# PART1.net
KiCad netlist of a schematic drawn in Altium Designer
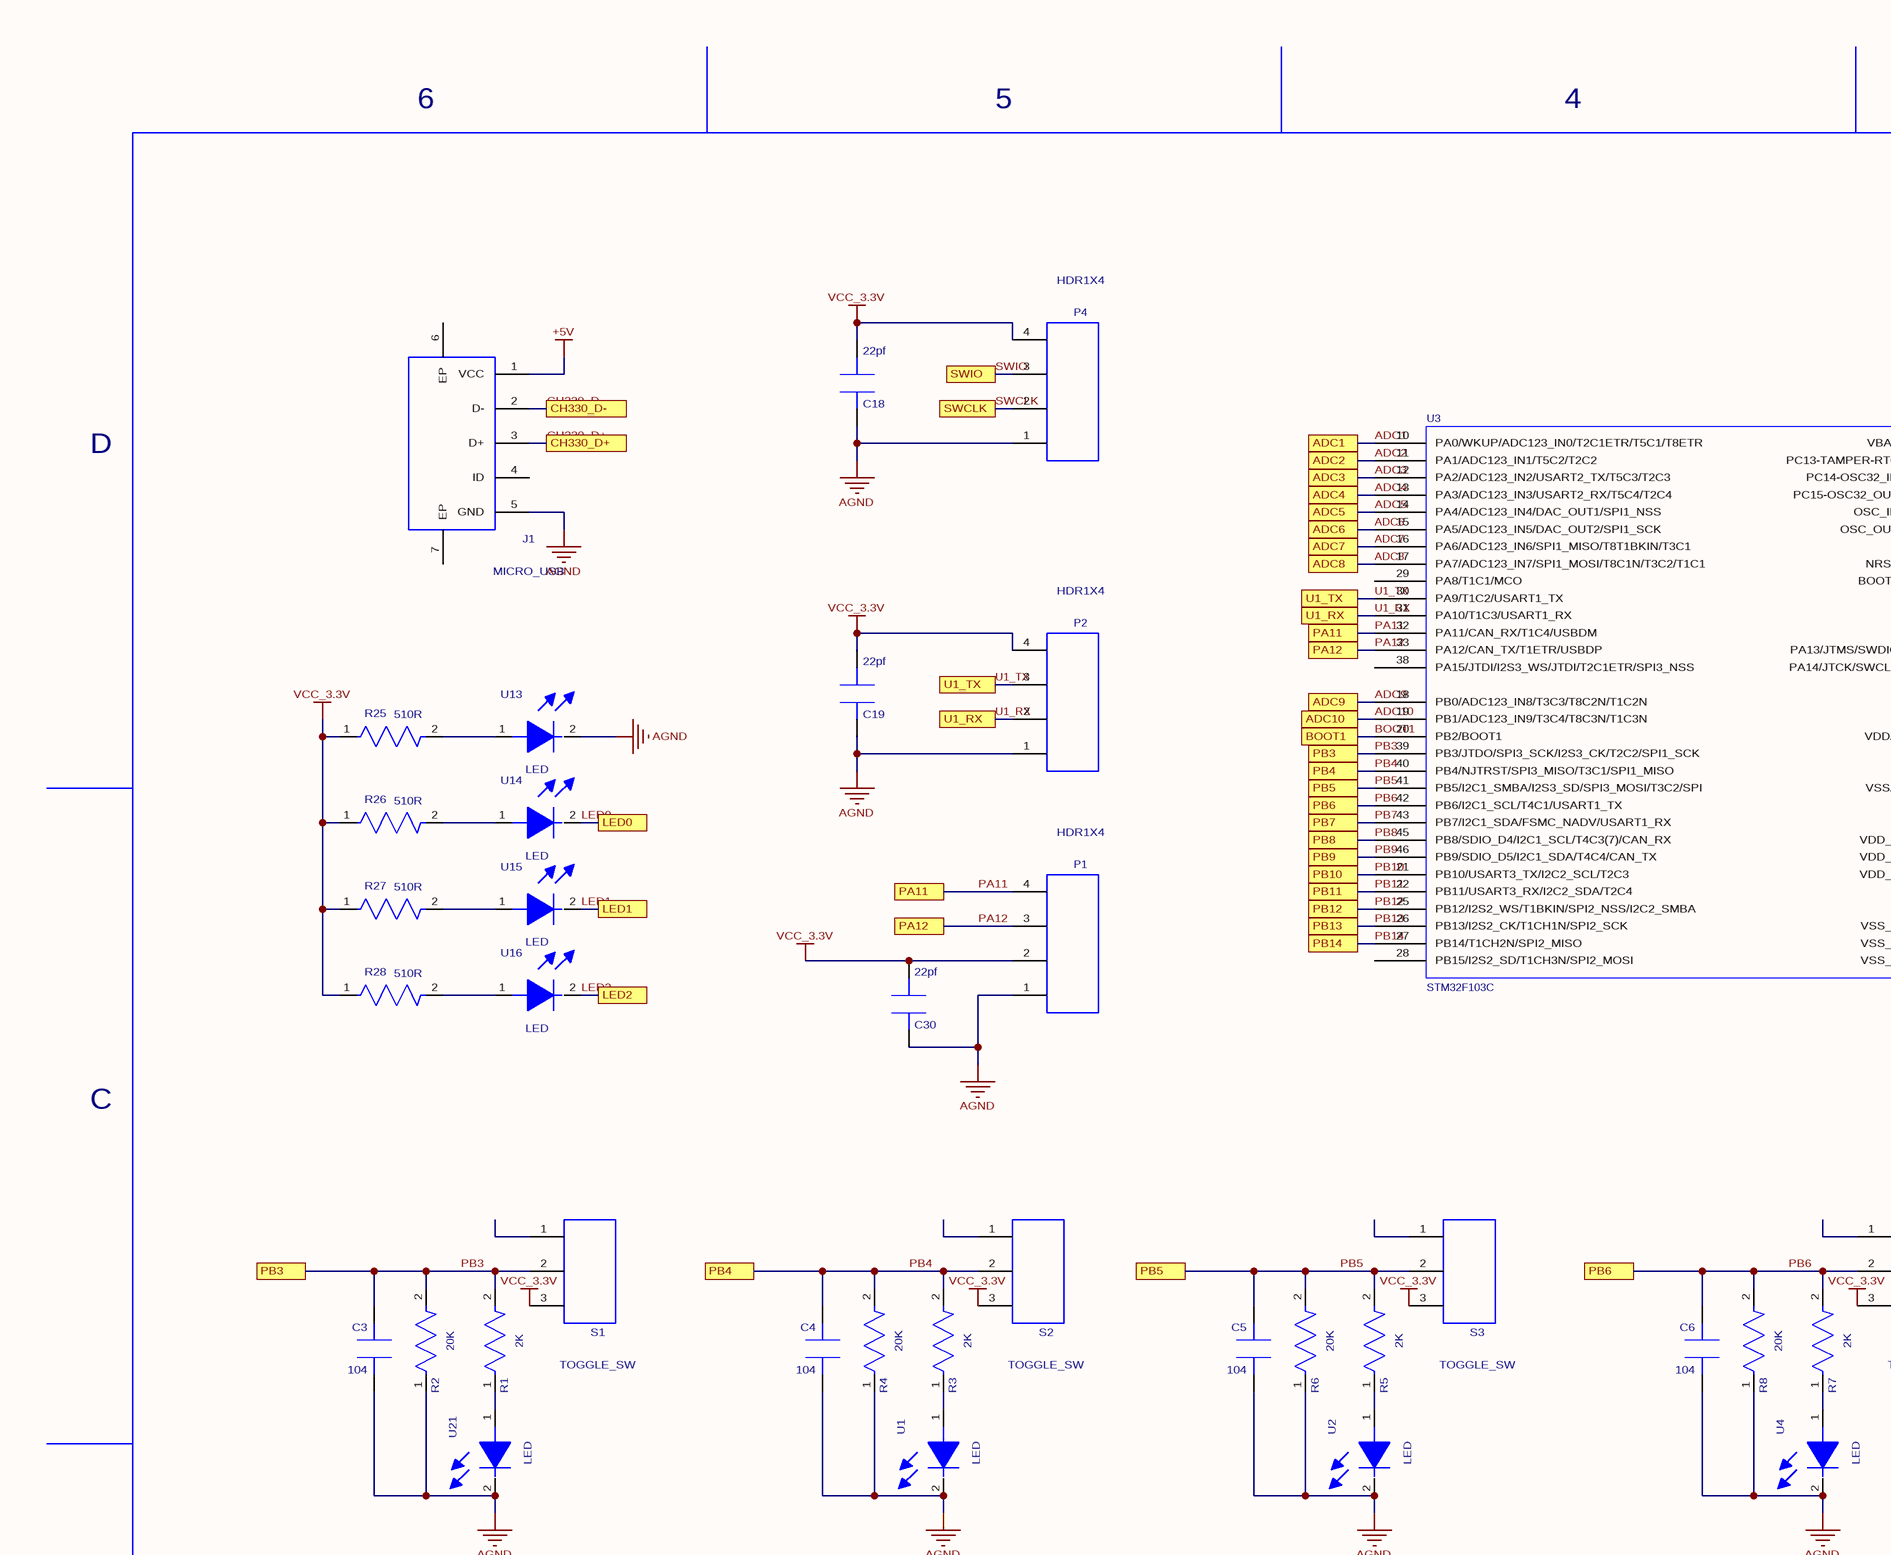
[diagram p0: PART1.SchDoc, top left]
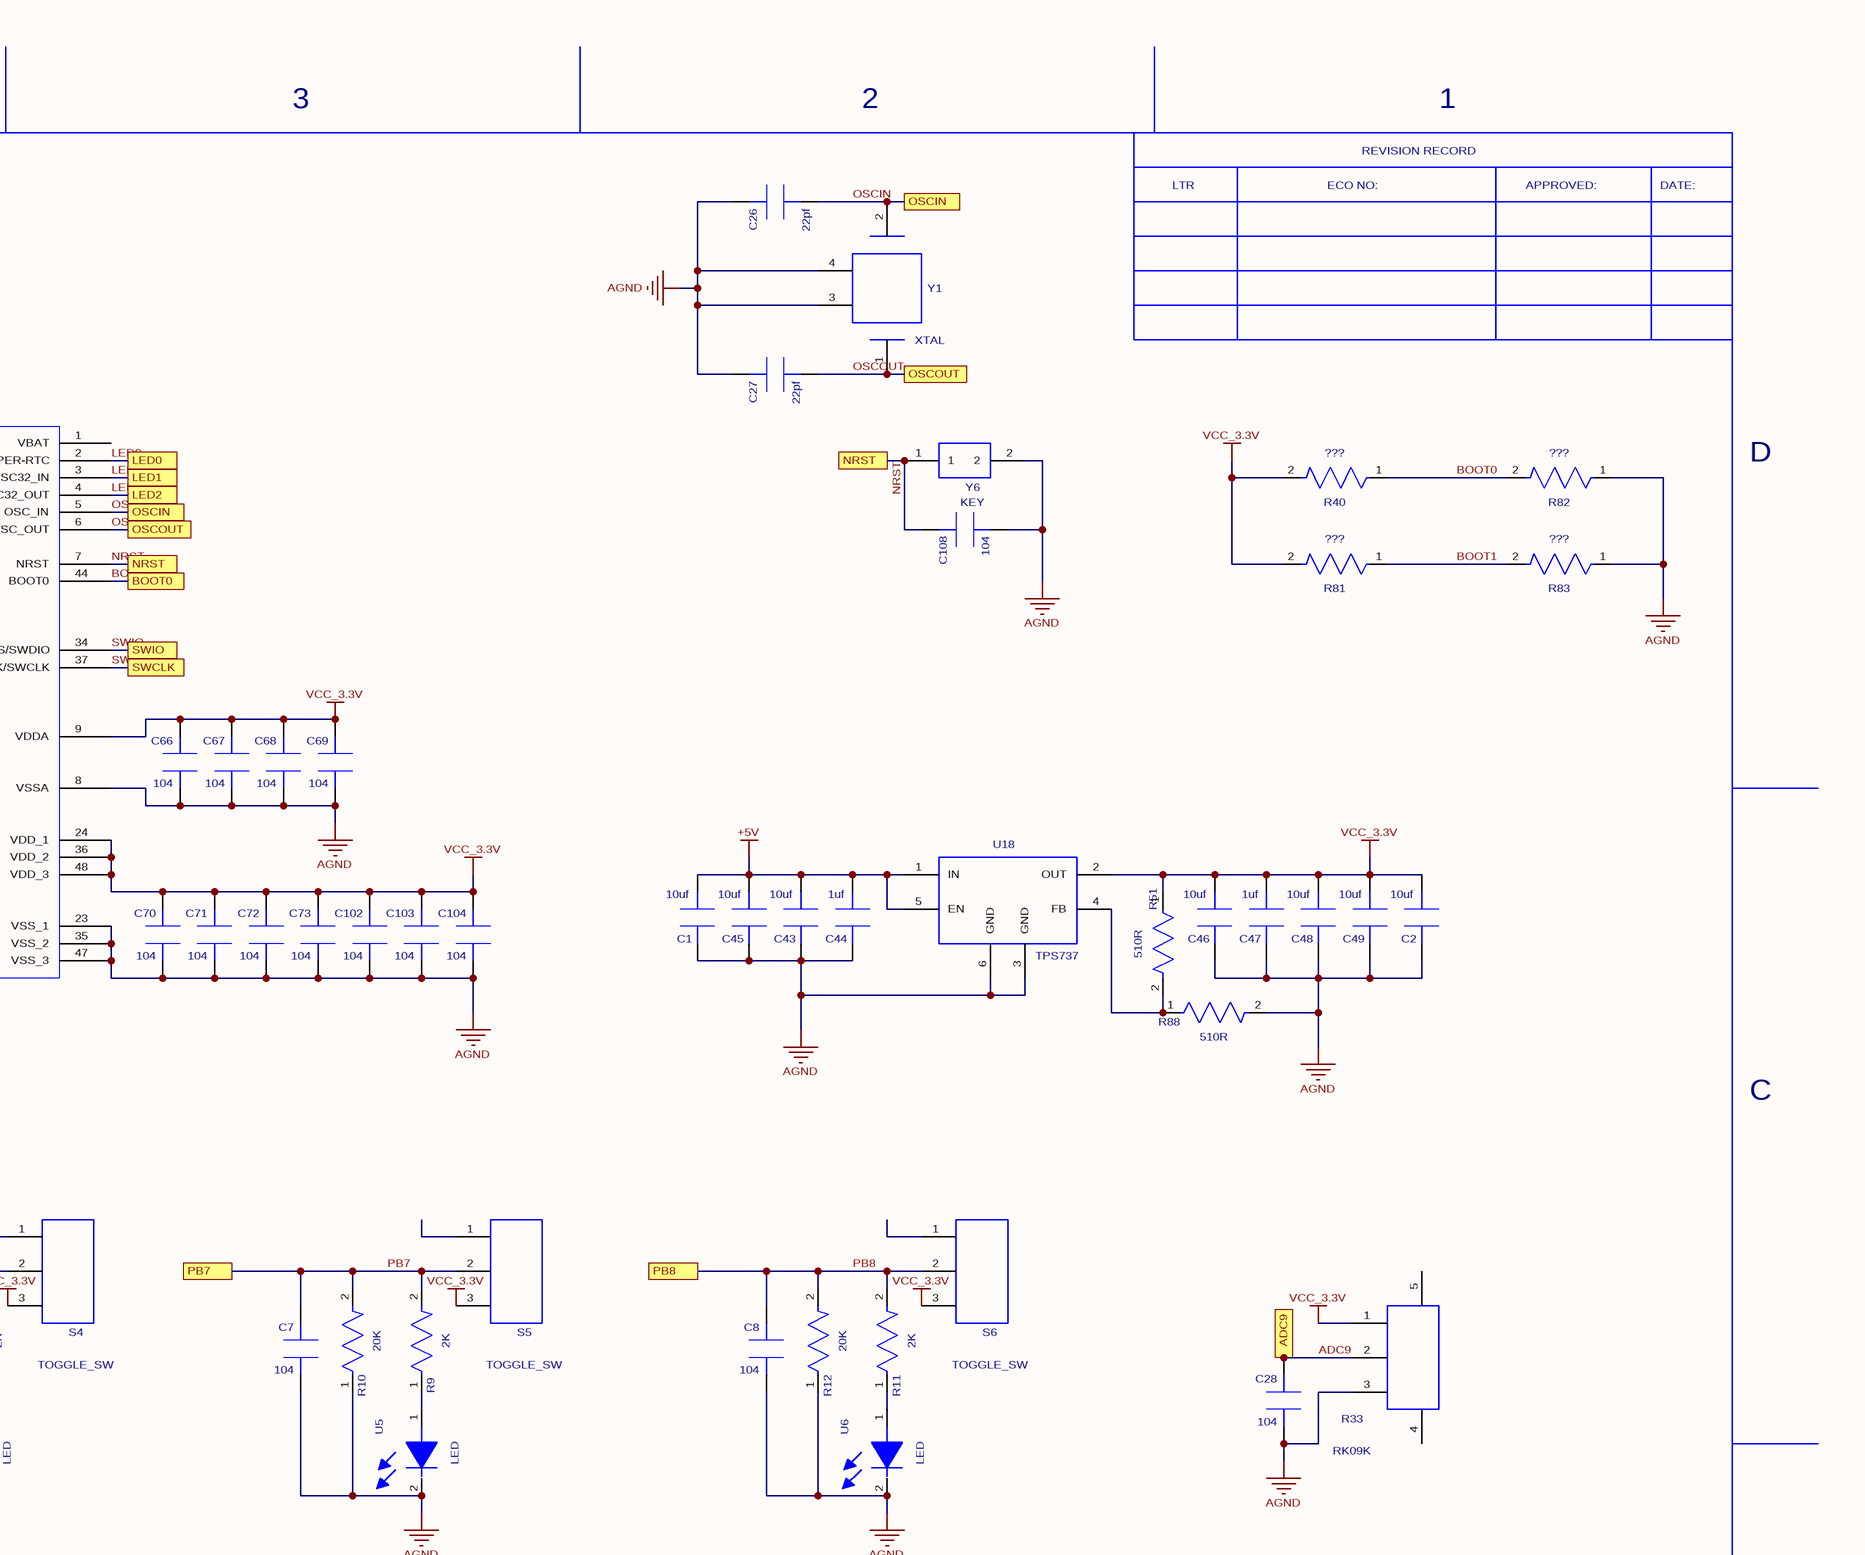
[diagram p1: PART1.SchDoc, top right]
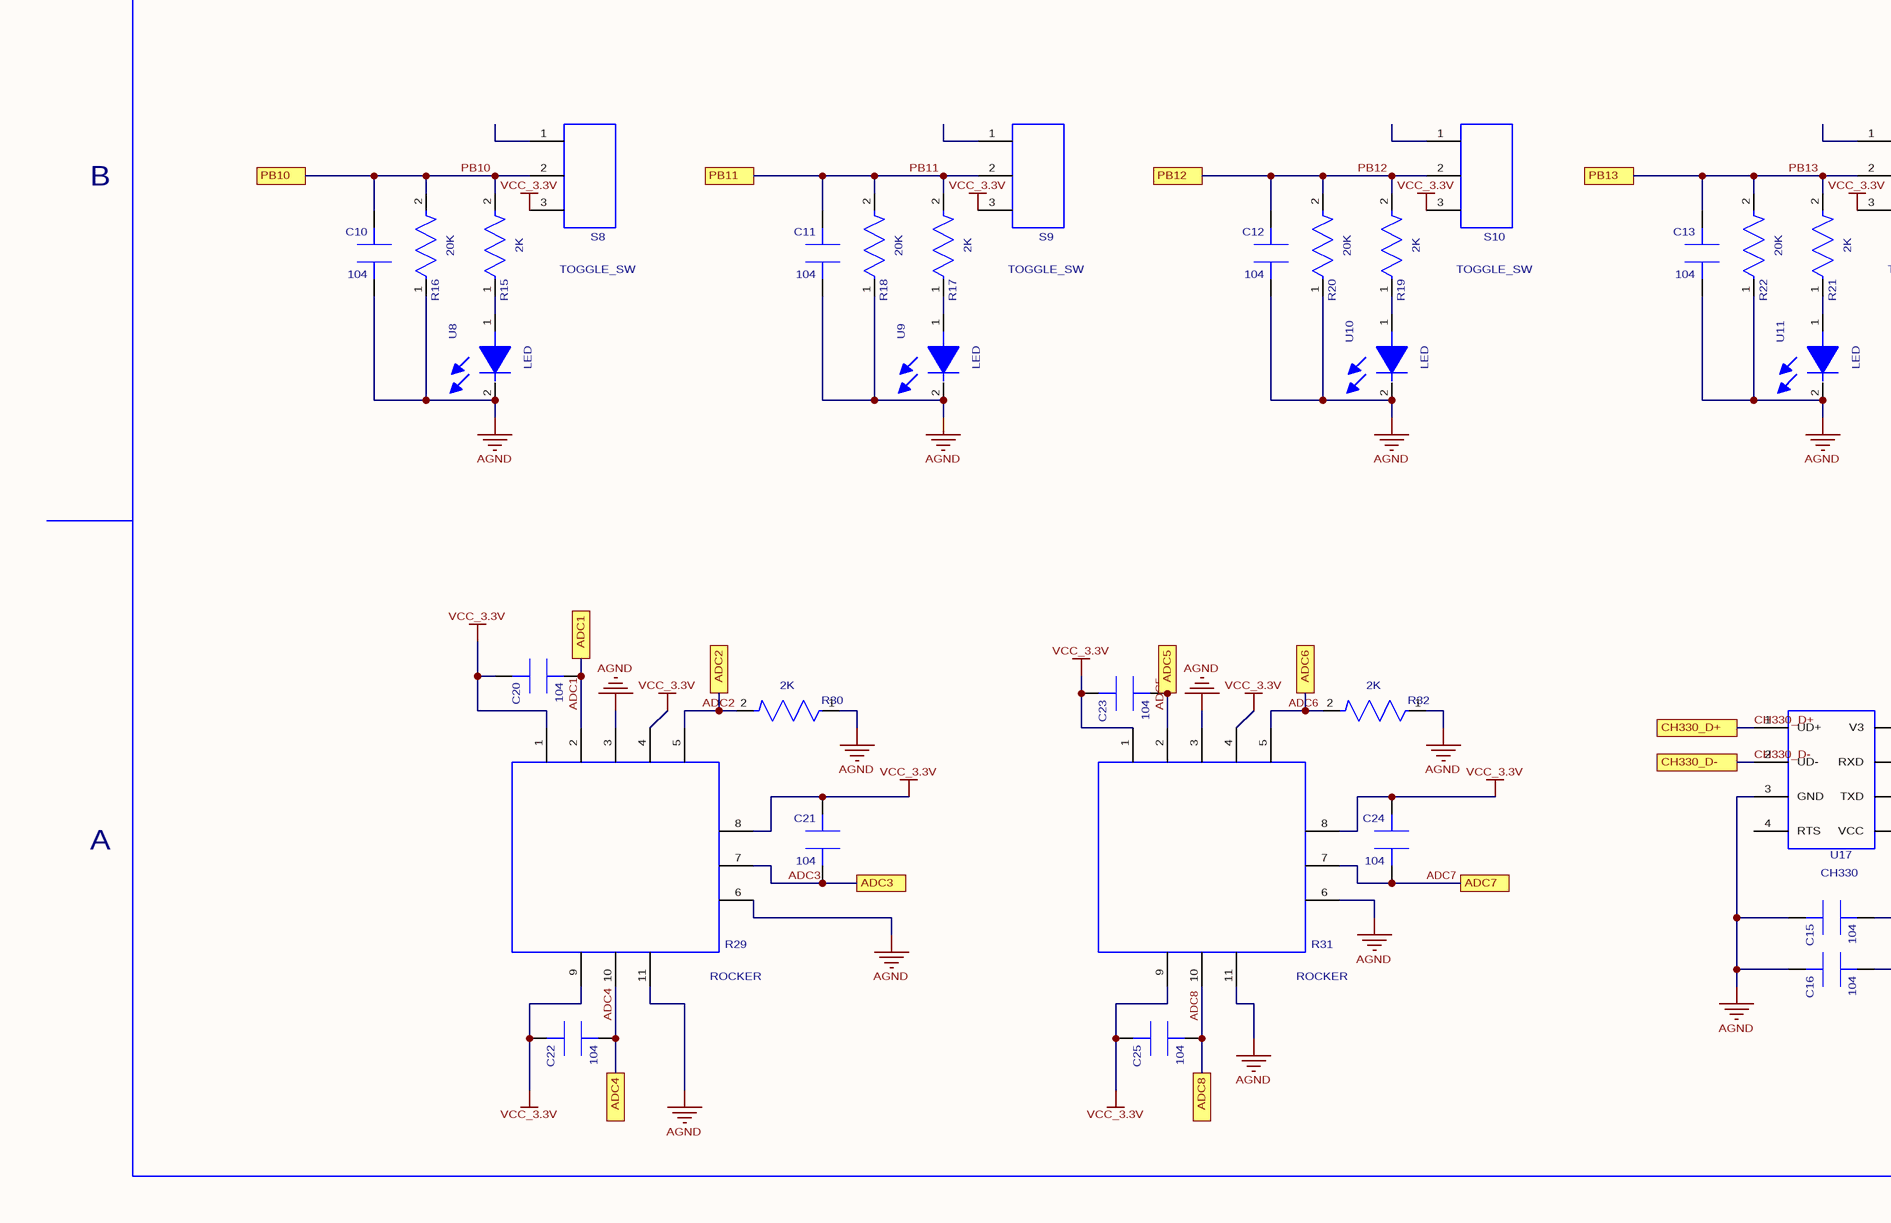
[diagram p2: PART1.SchDoc, bottom left]
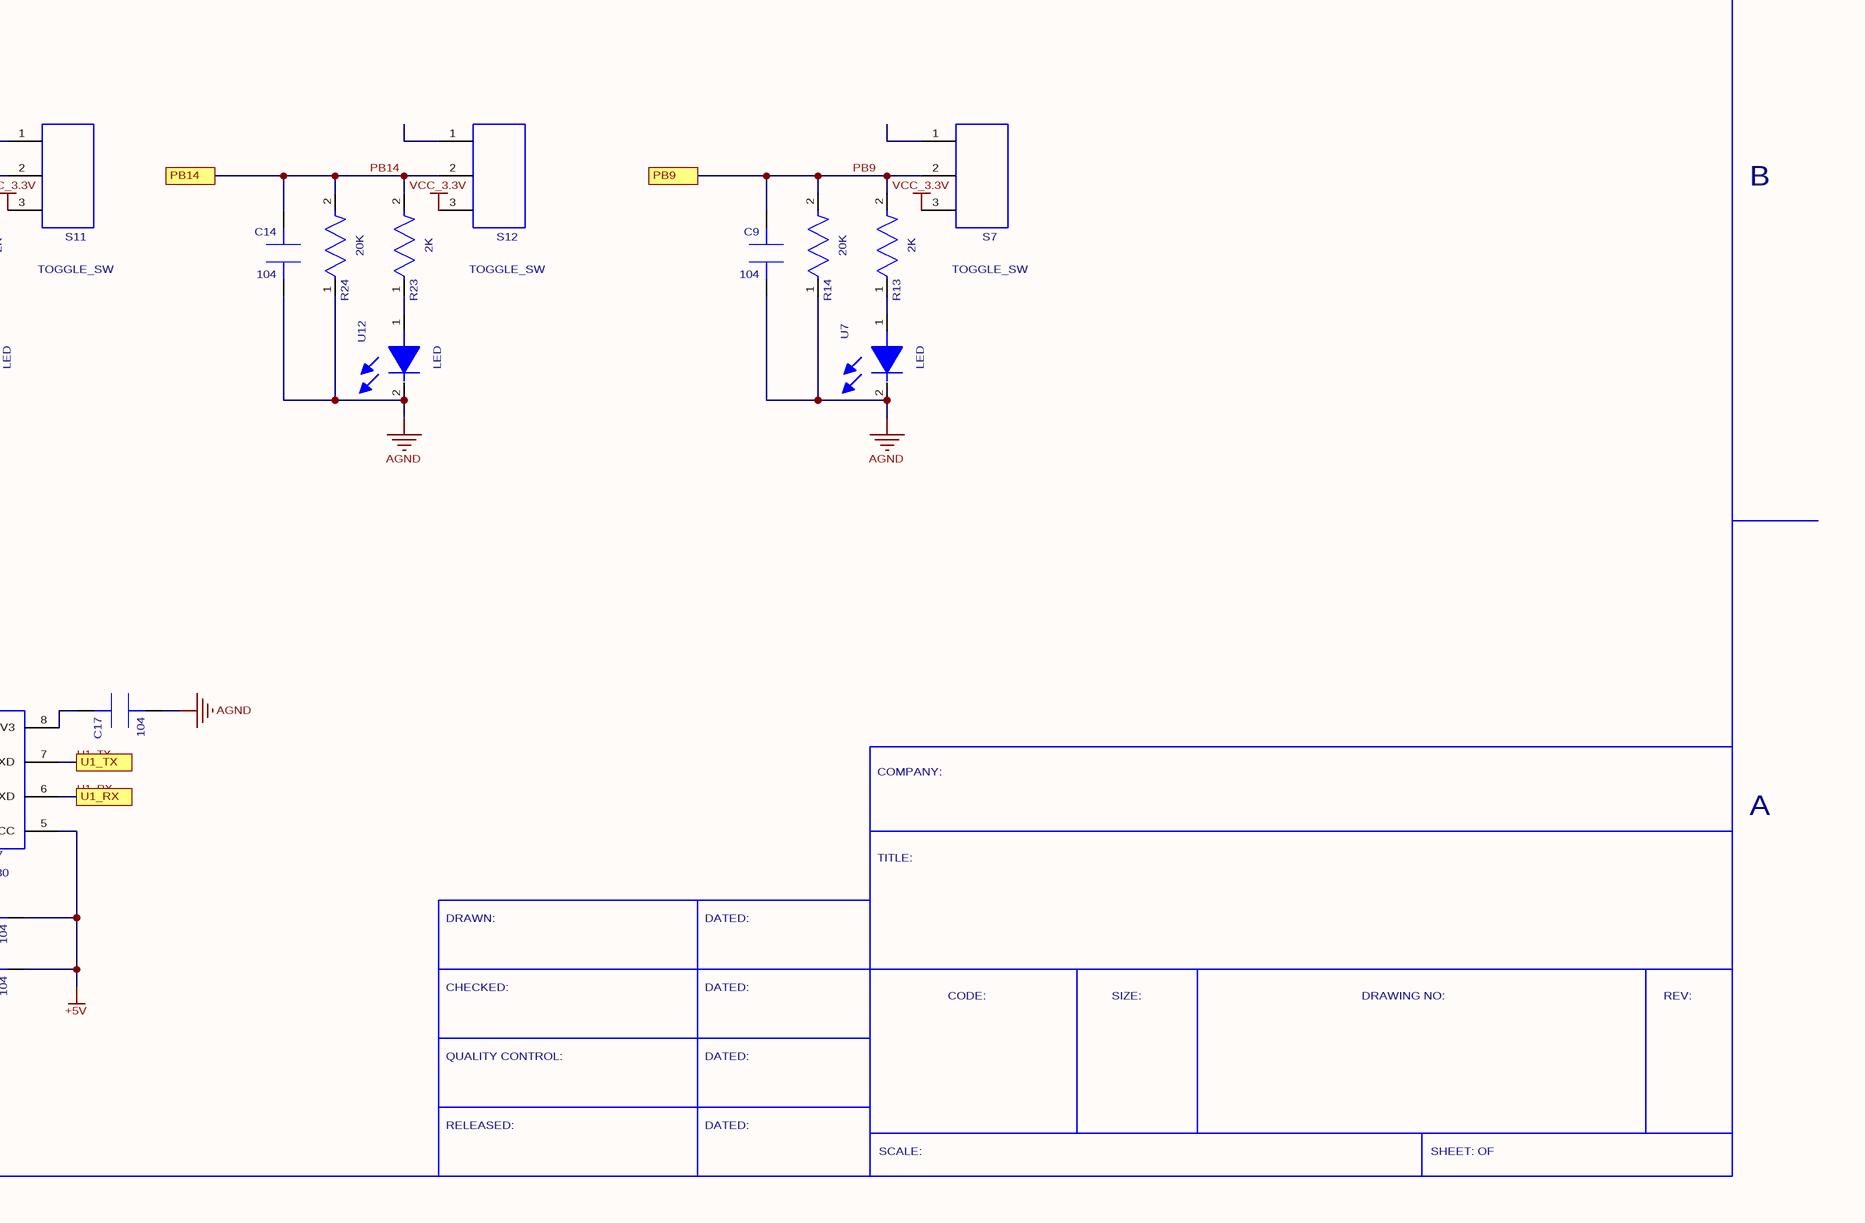
[diagram p3: PART1.SchDoc, bottom right]

(export (version "E")
  (design (tool "Eeschema 10.0.6"))
  (components
    (comp (ref "C1")
      (value "10uf")
      (footprint "1206C")
      (description "RADIAL FILM CAPACITOR, MIL-SPEC SIZE CFR04R SIZE 'C'")
      (fields (field (name "TOLERANCE") "???") (field (name "PART NUMBER") "TBD"))
      (libsource (lib "*") (part "CAP-CFR04R-C"))
    )
    (comp (ref "C2")
      (value "10uf")
      (footprint "1206C")
      (description "RADIAL FILM CAPACITOR, MIL-SPEC SIZE CFR04R SIZE 'C'")
      (fields (field (name "TOLERANCE") "???") (field (name "PART NUMBER") "TBD"))
      (libsource (lib "*") (part "CAP-CFR04R-C"))
    )
    (comp (ref "C3")
      (value "104")
      (footprint "0603C")
      (description "RADIAL FILM CAPACITOR, MIL-SPEC SIZE CFR04R SIZE 'C'")
      (fields (field (name "TOLERANCE") "???") (field (name "PART NUMBER") "TBD"))
      (libsource (lib "*") (part "CAP-CFR04R-C"))
    )
    (comp (ref "C4")
      (value "104")
      (footprint "0603C")
      (description "RADIAL FILM CAPACITOR, MIL-SPEC SIZE CFR04R SIZE 'C'")
      (fields (field (name "TOLERANCE") "???") (field (name "PART NUMBER") "TBD"))
      (libsource (lib "*") (part "CAP-CFR04R-C"))
    )
    (comp (ref "C5")
      (value "104")
      (footprint "0603C")
      (description "RADIAL FILM CAPACITOR, MIL-SPEC SIZE CFR04R SIZE 'C'")
      (fields (field (name "TOLERANCE") "???") (field (name "PART NUMBER") "TBD"))
      (libsource (lib "*") (part "CAP-CFR04R-C"))
    )
    (comp (ref "C6")
      (value "104")
      (footprint "0603C")
      (description "RADIAL FILM CAPACITOR, MIL-SPEC SIZE CFR04R SIZE 'C'")
      (fields (field (name "TOLERANCE") "???") (field (name "PART NUMBER") "TBD"))
      (libsource (lib "*") (part "CAP-CFR04R-C"))
    )
    (comp (ref "C7")
      (value "104")
      (footprint "0603C")
      (description "RADIAL FILM CAPACITOR, MIL-SPEC SIZE CFR04R SIZE 'C'")
      (fields (field (name "TOLERANCE") "???") (field (name "PART NUMBER") "TBD"))
      (libsource (lib "*") (part "CAP-CFR04R-C"))
    )
    (comp (ref "C8")
      (value "104")
      (footprint "0603C")
      (description "RADIAL FILM CAPACITOR, MIL-SPEC SIZE CFR04R SIZE 'C'")
      (fields (field (name "TOLERANCE") "???") (field (name "PART NUMBER") "TBD"))
      (libsource (lib "*") (part "CAP-CFR04R-C"))
    )
    (comp (ref "C9")
      (value "104")
      (footprint "0603C")
      (description "RADIAL FILM CAPACITOR, MIL-SPEC SIZE CFR04R SIZE 'C'")
      (fields (field (name "TOLERANCE") "???") (field (name "PART NUMBER") "TBD"))
      (libsource (lib "*") (part "CAP-CFR04R-C"))
    )
    (comp (ref "C10")
      (value "104")
      (footprint "0603C")
      (description "RADIAL FILM CAPACITOR, MIL-SPEC SIZE CFR04R SIZE 'C'")
      (fields (field (name "TOLERANCE") "???") (field (name "PART NUMBER") "TBD"))
      (libsource (lib "*") (part "CAP-CFR04R-C"))
    )
    (comp (ref "C11")
      (value "104")
      (footprint "0603C")
      (description "RADIAL FILM CAPACITOR, MIL-SPEC SIZE CFR04R SIZE 'C'")
      (fields (field (name "TOLERANCE") "???") (field (name "PART NUMBER") "TBD"))
      (libsource (lib "*") (part "CAP-CFR04R-C"))
    )
    (comp (ref "C12")
      (value "104")
      (footprint "0603C")
      (description "RADIAL FILM CAPACITOR, MIL-SPEC SIZE CFR04R SIZE 'C'")
      (fields (field (name "TOLERANCE") "???") (field (name "PART NUMBER") "TBD"))
      (libsource (lib "*") (part "CAP-CFR04R-C"))
    )
    (comp (ref "C13")
      (value "104")
      (footprint "0603C")
      (description "RADIAL FILM CAPACITOR, MIL-SPEC SIZE CFR04R SIZE 'C'")
      (fields (field (name "TOLERANCE") "???") (field (name "PART NUMBER") "TBD"))
      (libsource (lib "*") (part "CAP-CFR04R-C"))
    )
    (comp (ref "C14")
      (value "104")
      (footprint "0603C")
      (description "RADIAL FILM CAPACITOR, MIL-SPEC SIZE CFR04R SIZE 'C'")
      (fields (field (name "TOLERANCE") "???") (field (name "PART NUMBER") "TBD"))
      (libsource (lib "*") (part "CAP-CFR04R-C"))
    )
    (comp (ref "C15")
      (value "104")
      (footprint "0603C")
      (description "RADIAL FILM CAPACITOR, MIL-SPEC SIZE CFR04R SIZE 'C'")
      (fields (field (name "TOLERANCE") "???") (field (name "PART NUMBER") "TBD"))
      (libsource (lib "*") (part "CAP-CFR04R-C"))
    )
    (comp (ref "C16")
      (value "104")
      (footprint "0805C")
      (description "RADIAL FILM CAPACITOR, MIL-SPEC SIZE CFR04R SIZE 'C'")
      (fields (field (name "TOLERANCE") "???") (field (name "PART NUMBER") "TBD"))
      (libsource (lib "*") (part "CAP-CFR04R-C"))
    )
    (comp (ref "C17")
      (value "104")
      (footprint "0603C")
      (description "RADIAL FILM CAPACITOR, MIL-SPEC SIZE CFR04R SIZE 'C'")
      (fields (field (name "TOLERANCE") "???") (field (name "PART NUMBER") "TBD"))
      (libsource (lib "*") (part "CAP-CFR04R-C"))
    )
    (comp (ref "C18")
      (value "22pf")
      (footprint "0603C")
      (description "RADIAL FILM CAPACITOR, MIL-SPEC SIZE CFR04R SIZE 'C'")
      (fields (field (name "TOLERANCE") "???") (field (name "PART NUMBER") "TBD"))
      (libsource (lib "*") (part "CAP-CFR04R-C"))
    )
    (comp (ref "C19")
      (value "22pf")
      (footprint "0603C")
      (description "RADIAL FILM CAPACITOR, MIL-SPEC SIZE CFR04R SIZE 'C'")
      (fields (field (name "TOLERANCE") "???") (field (name "PART NUMBER") "TBD"))
      (libsource (lib "*") (part "CAP-CFR04R-C"))
    )
    (comp (ref "C20")
      (value "104")
      (footprint "0805C")
      (description "RADIAL FILM CAPACITOR, MIL-SPEC SIZE CFR04R SIZE 'C'")
      (fields (field (name "TOLERANCE") "???") (field (name "PART NUMBER") "TBD"))
      (libsource (lib "*") (part "CAP-CFR04R-C"))
    )
    (comp (ref "C21")
      (value "104")
      (footprint "0805C")
      (description "RADIAL FILM CAPACITOR, MIL-SPEC SIZE CFR04R SIZE 'C'")
      (fields (field (name "TOLERANCE") "???") (field (name "PART NUMBER") "TBD"))
      (libsource (lib "*") (part "CAP-CFR04R-C"))
    )
    (comp (ref "C22")
      (value "104")
      (footprint "0805C")
      (description "RADIAL FILM CAPACITOR, MIL-SPEC SIZE CFR04R SIZE 'C'")
      (fields (field (name "TOLERANCE") "???") (field (name "PART NUMBER") "TBD"))
      (libsource (lib "*") (part "CAP-CFR04R-C"))
    )
    (comp (ref "C23")
      (value "104")
      (footprint "0805C")
      (description "RADIAL FILM CAPACITOR, MIL-SPEC SIZE CFR04R SIZE 'C'")
      (fields (field (name "TOLERANCE") "???") (field (name "PART NUMBER") "TBD"))
      (libsource (lib "*") (part "CAP-CFR04R-C"))
    )
    (comp (ref "C24")
      (value "104")
      (footprint "0805C")
      (description "RADIAL FILM CAPACITOR, MIL-SPEC SIZE CFR04R SIZE 'C'")
      (fields (field (name "TOLERANCE") "???") (field (name "PART NUMBER") "TBD"))
      (libsource (lib "*") (part "CAP-CFR04R-C"))
    )
    (comp (ref "C25")
      (value "104")
      (footprint "0805C")
      (description "RADIAL FILM CAPACITOR, MIL-SPEC SIZE CFR04R SIZE 'C'")
      (fields (field (name "TOLERANCE") "???") (field (name "PART NUMBER") "TBD"))
      (libsource (lib "*") (part "CAP-CFR04R-C"))
    )
    (comp (ref "C26")
      (value "22pf")
      (footprint "0603C")
      (description "RADIAL FILM CAPACITOR, MIL-SPEC SIZE CFR04R SIZE 'C'")
      (fields (field (name "TOLERANCE") "???") (field (name "PART NUMBER") "TBD"))
      (libsource (lib "*") (part "CAP-CFR04R-C"))
    )
    (comp (ref "C27")
      (value "22pf")
      (footprint "0603C")
      (description "RADIAL FILM CAPACITOR, MIL-SPEC SIZE CFR04R SIZE 'C'")
      (fields (field (name "TOLERANCE") "???") (field (name "PART NUMBER") "TBD"))
      (libsource (lib "*") (part "CAP-CFR04R-C"))
    )
    (comp (ref "C28")
      (value "104")
      (footprint "0603C")
      (description "RADIAL FILM CAPACITOR, MIL-SPEC SIZE CFR04R SIZE 'C'")
      (fields (field (name "TOLERANCE") "???") (field (name "PART NUMBER") "TBD"))
      (libsource (lib "*") (part "CAP-CFR04R-C"))
    )
    (comp (ref "C30")
      (value "22pf")
      (footprint "0603C")
      (description "RADIAL FILM CAPACITOR, MIL-SPEC SIZE CFR04R SIZE 'C'")
      (fields (field (name "TOLERANCE") "???") (field (name "PART NUMBER") "TBD"))
      (libsource (lib "*") (part "CAP-CFR04R-C"))
    )
    (comp (ref "C43")
      (value "10uf")
      (footprint "1206C")
      (description "RADIAL FILM CAPACITOR, MIL-SPEC SIZE CFR04R SIZE 'C'")
      (fields (field (name "TOLERANCE") "???") (field (name "PART NUMBER") "TBD"))
      (libsource (lib "*") (part "CAP-CFR04R-C"))
    )
    (comp (ref "C44")
      (value "1uf")
      (footprint "0805C")
      (description "RADIAL FILM CAPACITOR, MIL-SPEC SIZE CFR04R SIZE 'C'")
      (fields (field (name "TOLERANCE") "???") (field (name "PART NUMBER") "TBD"))
      (libsource (lib "*") (part "CAP-CFR04R-C"))
    )
    (comp (ref "C45")
      (value "10uf")
      (footprint "1206C")
      (description "RADIAL FILM CAPACITOR, MIL-SPEC SIZE CFR04R SIZE 'C'")
      (fields (field (name "TOLERANCE") "???") (field (name "PART NUMBER") "TBD"))
      (libsource (lib "*") (part "CAP-CFR04R-C"))
    )
    (comp (ref "C46")
      (value "10uf")
      (footprint "1206C")
      (description "RADIAL FILM CAPACITOR, MIL-SPEC SIZE CFR04R SIZE 'C'")
      (fields (field (name "TOLERANCE") "???") (field (name "PART NUMBER") "TBD"))
      (libsource (lib "*") (part "CAP-CFR04R-C"))
    )
    (comp (ref "C47")
      (value "1uf")
      (footprint "0805C")
      (description "RADIAL FILM CAPACITOR, MIL-SPEC SIZE CFR04R SIZE 'C'")
      (fields (field (name "TOLERANCE") "???") (field (name "PART NUMBER") "TBD"))
      (libsource (lib "*") (part "CAP-CFR04R-C"))
    )
    (comp (ref "C48")
      (value "10uf")
      (footprint "1206C")
      (description "RADIAL FILM CAPACITOR, MIL-SPEC SIZE CFR04R SIZE 'C'")
      (fields (field (name "TOLERANCE") "???") (field (name "PART NUMBER") "TBD"))
      (libsource (lib "*") (part "CAP-CFR04R-C"))
    )
    (comp (ref "C49")
      (value "10uf")
      (footprint "1206C")
      (description "RADIAL FILM CAPACITOR, MIL-SPEC SIZE CFR04R SIZE 'C'")
      (fields (field (name "TOLERANCE") "???") (field (name "PART NUMBER") "TBD"))
      (libsource (lib "*") (part "CAP-CFR04R-C"))
    )
    (comp (ref "C66")
      (value "104")
      (footprint "0805C")
      (description "RADIAL FILM CAPACITOR, MIL-SPEC SIZE CFR04R SIZE 'C'")
      (fields (field (name "TOLERANCE") "???") (field (name "PART NUMBER") "TBD"))
      (libsource (lib "*") (part "CAP-CFR04R-C"))
    )
    (comp (ref "C67")
      (value "104")
      (footprint "0805C")
      (description "RADIAL FILM CAPACITOR, MIL-SPEC SIZE CFR04R SIZE 'C'")
      (fields (field (name "TOLERANCE") "???") (field (name "PART NUMBER") "TBD"))
      (libsource (lib "*") (part "CAP-CFR04R-C"))
    )
    (comp (ref "C68")
      (value "104")
      (footprint "0805C")
      (description "RADIAL FILM CAPACITOR, MIL-SPEC SIZE CFR04R SIZE 'C'")
      (fields (field (name "TOLERANCE") "???") (field (name "PART NUMBER") "TBD"))
      (libsource (lib "*") (part "CAP-CFR04R-C"))
    )
    (comp (ref "C69")
      (value "104")
      (footprint "0805C")
      (description "RADIAL FILM CAPACITOR, MIL-SPEC SIZE CFR04R SIZE 'C'")
      (fields (field (name "TOLERANCE") "???") (field (name "PART NUMBER") "TBD"))
      (libsource (lib "*") (part "CAP-CFR04R-C"))
    )
    (comp (ref "C70")
      (value "104")
      (footprint "0805C")
      (description "RADIAL FILM CAPACITOR, MIL-SPEC SIZE CFR04R SIZE 'C'")
      (fields (field (name "TOLERANCE") "???") (field (name "PART NUMBER") "TBD"))
      (libsource (lib "*") (part "CAP-CFR04R-C"))
    )
    (comp (ref "C71")
      (value "104")
      (footprint "0805C")
      (description "RADIAL FILM CAPACITOR, MIL-SPEC SIZE CFR04R SIZE 'C'")
      (fields (field (name "TOLERANCE") "???") (field (name "PART NUMBER") "TBD"))
      (libsource (lib "*") (part "CAP-CFR04R-C"))
    )
    (comp (ref "C72")
      (value "104")
      (footprint "0805C")
      (description "RADIAL FILM CAPACITOR, MIL-SPEC SIZE CFR04R SIZE 'C'")
      (fields (field (name "TOLERANCE") "???") (field (name "PART NUMBER") "TBD"))
      (libsource (lib "*") (part "CAP-CFR04R-C"))
    )
    (comp (ref "C73")
      (value "104")
      (footprint "0805C")
      (description "RADIAL FILM CAPACITOR, MIL-SPEC SIZE CFR04R SIZE 'C'")
      (fields (field (name "TOLERANCE") "???") (field (name "PART NUMBER") "TBD"))
      (libsource (lib "*") (part "CAP-CFR04R-C"))
    )
    (comp (ref "C102")
      (value "104")
      (footprint "0805C")
      (description "RADIAL FILM CAPACITOR, MIL-SPEC SIZE CFR04R SIZE 'C'")
      (fields (field (name "TOLERANCE") "???") (field (name "PART NUMBER") "TBD"))
      (libsource (lib "*") (part "CAP-CFR04R-C"))
    )
    (comp (ref "C103")
      (value "104")
      (footprint "0805C")
      (description "RADIAL FILM CAPACITOR, MIL-SPEC SIZE CFR04R SIZE 'C'")
      (fields (field (name "TOLERANCE") "???") (field (name "PART NUMBER") "TBD"))
      (libsource (lib "*") (part "CAP-CFR04R-C"))
    )
    (comp (ref "C104")
      (value "104")
      (footprint "0805C")
      (description "RADIAL FILM CAPACITOR, MIL-SPEC SIZE CFR04R SIZE 'C'")
      (fields (field (name "TOLERANCE") "???") (field (name "PART NUMBER") "TBD"))
      (libsource (lib "*") (part "CAP-CFR04R-C"))
    )
    (comp (ref "C108")
      (value "104")
      (footprint "0805C")
      (description "RADIAL FILM CAPACITOR, MIL-SPEC SIZE CFR04R SIZE 'C'")
      (fields (field (name "TOLERANCE") "???") (field (name "PART NUMBER") "TBD"))
      (libsource (lib "*") (part "CAP-CFR04R-C"))
    )
    (comp (ref "J1") (value "MICRO_USB") (footprint "MICRO_USB") (libsource (lib "*") (part "MICRO_USB")))
    (comp (ref "P1") (value "HDR1X4") (footprint "HDR1X4(2)") (libsource (lib "*") (part "HDR1X4")))
    (comp (ref "P2") (value "HDR1X4") (footprint "HDR1X4(2)") (libsource (lib "*") (part "HDR1X4")))
    (comp (ref "P4") (value "HDR1X4") (footprint "HDR1X4(2)") (libsource (lib "*") (part "HDR1X4")))
    (comp (ref "R1")
      (value "2K")
      (footprint "0603R")
      (description "WIRE WOUND RESISTOR 3.4 X 7.05 MM")
      (fields (field (name "Comment") "RES-WR1"))
      (libsource (lib "*") (part "RES-WR1"))
    )
    (comp (ref "R2")
      (value "20K")
      (footprint "0603R")
      (description "WIRE WOUND RESISTOR 3.4 X 7.05 MM")
      (fields (field (name "Comment") "RES-WR1"))
      (libsource (lib "*") (part "RES-WR1"))
    )
    (comp (ref "R3")
      (value "2K")
      (footprint "0603R")
      (description "WIRE WOUND RESISTOR 3.4 X 7.05 MM")
      (fields (field (name "Comment") "RES-WR1"))
      (libsource (lib "*") (part "RES-WR1"))
    )
    (comp (ref "R4")
      (value "20K")
      (footprint "0603R")
      (description "WIRE WOUND RESISTOR 3.4 X 7.05 MM")
      (fields (field (name "Comment") "RES-WR1"))
      (libsource (lib "*") (part "RES-WR1"))
    )
    (comp (ref "R5")
      (value "2K")
      (footprint "0603R")
      (description "WIRE WOUND RESISTOR 3.4 X 7.05 MM")
      (fields (field (name "Comment") "RES-WR1"))
      (libsource (lib "*") (part "RES-WR1"))
    )
    (comp (ref "R6")
      (value "20K")
      (footprint "0603R")
      (description "WIRE WOUND RESISTOR 3.4 X 7.05 MM")
      (fields (field (name "Comment") "RES-WR1"))
      (libsource (lib "*") (part "RES-WR1"))
    )
    (comp (ref "R7")
      (value "2K")
      (footprint "0603R")
      (description "WIRE WOUND RESISTOR 3.4 X 7.05 MM")
      (fields (field (name "Comment") "RES-WR1"))
      (libsource (lib "*") (part "RES-WR1"))
    )
    (comp (ref "R8")
      (value "20K")
      (footprint "0603R")
      (description "WIRE WOUND RESISTOR 3.4 X 7.05 MM")
      (fields (field (name "Comment") "RES-WR1"))
      (libsource (lib "*") (part "RES-WR1"))
    )
    (comp (ref "R9")
      (value "2K")
      (footprint "0603R")
      (description "WIRE WOUND RESISTOR 3.4 X 7.05 MM")
      (fields (field (name "Comment") "RES-WR1"))
      (libsource (lib "*") (part "RES-WR1"))
    )
    (comp (ref "R10")
      (value "20K")
      (footprint "0603R")
      (description "WIRE WOUND RESISTOR 3.4 X 7.05 MM")
      (fields (field (name "Comment") "RES-WR1"))
      (libsource (lib "*") (part "RES-WR1"))
    )
    (comp (ref "R11")
      (value "2K")
      (footprint "0603R")
      (description "WIRE WOUND RESISTOR 3.4 X 7.05 MM")
      (fields (field (name "Comment") "RES-WR1"))
      (libsource (lib "*") (part "RES-WR1"))
    )
    (comp (ref "R12")
      (value "20K")
      (footprint "0603R")
      (description "WIRE WOUND RESISTOR 3.4 X 7.05 MM")
      (fields (field (name "Comment") "RES-WR1"))
      (libsource (lib "*") (part "RES-WR1"))
    )
    (comp (ref "R13")
      (value "2K")
      (footprint "0603R")
      (description "WIRE WOUND RESISTOR 3.4 X 7.05 MM")
      (fields (field (name "Comment") "RES-WR1"))
      (libsource (lib "*") (part "RES-WR1"))
    )
    (comp (ref "R14")
      (value "20K")
      (footprint "0603R")
      (description "WIRE WOUND RESISTOR 3.4 X 7.05 MM")
      (fields (field (name "Comment") "RES-WR1"))
      (libsource (lib "*") (part "RES-WR1"))
    )
    (comp (ref "R15")
      (value "2K")
      (footprint "0603R")
      (description "WIRE WOUND RESISTOR 3.4 X 7.05 MM")
      (fields (field (name "Comment") "RES-WR1"))
      (libsource (lib "*") (part "RES-WR1"))
    )
    (comp (ref "R16")
      (value "20K")
      (footprint "0603R")
      (description "WIRE WOUND RESISTOR 3.4 X 7.05 MM")
      (fields (field (name "Comment") "RES-WR1"))
      (libsource (lib "*") (part "RES-WR1"))
    )
    (comp (ref "R17")
      (value "2K")
      (footprint "0603R")
      (description "WIRE WOUND RESISTOR 3.4 X 7.05 MM")
      (fields (field (name "Comment") "RES-WR1"))
      (libsource (lib "*") (part "RES-WR1"))
    )
    (comp (ref "R18")
      (value "20K")
      (footprint "0603R")
      (description "WIRE WOUND RESISTOR 3.4 X 7.05 MM")
      (fields (field (name "Comment") "RES-WR1"))
      (libsource (lib "*") (part "RES-WR1"))
    )
    (comp (ref "R19")
      (value "2K")
      (footprint "0603R")
      (description "WIRE WOUND RESISTOR 3.4 X 7.05 MM")
      (fields (field (name "Comment") "RES-WR1"))
      (libsource (lib "*") (part "RES-WR1"))
    )
    (comp (ref "R20")
      (value "20K")
      (footprint "0603R")
      (description "WIRE WOUND RESISTOR 3.4 X 7.05 MM")
      (fields (field (name "Comment") "RES-WR1"))
      (libsource (lib "*") (part "RES-WR1"))
    )
    (comp (ref "R21")
      (value "2K")
      (footprint "0603R")
      (description "WIRE WOUND RESISTOR 3.4 X 7.05 MM")
      (fields (field (name "Comment") "RES-WR1"))
      (libsource (lib "*") (part "RES-WR1"))
    )
    (comp (ref "R22")
      (value "20K")
      (footprint "0603R")
      (description "WIRE WOUND RESISTOR 3.4 X 7.05 MM")
      (fields (field (name "Comment") "RES-WR1"))
      (libsource (lib "*") (part "RES-WR1"))
    )
    (comp (ref "R23")
      (value "2K")
      (footprint "0603R")
      (description "WIRE WOUND RESISTOR 3.4 X 7.05 MM")
      (fields (field (name "Comment") "RES-WR1"))
      (libsource (lib "*") (part "RES-WR1"))
    )
    (comp (ref "R24")
      (value "20K")
      (footprint "0603R")
      (description "WIRE WOUND RESISTOR 3.4 X 7.05 MM")
      (fields (field (name "Comment") "RES-WR1"))
      (libsource (lib "*") (part "RES-WR1"))
    )
    (comp (ref "R25")
      (value "510R")
      (footprint "0603R")
      (description "WIRE WOUND RESISTOR 3.4 X 7.05 MM")
      (fields (field (name "Comment") "RES-WR1"))
      (libsource (lib "*") (part "RES-WR1"))
    )
    (comp (ref "R26")
      (value "510R")
      (footprint "0603R")
      (description "WIRE WOUND RESISTOR 3.4 X 7.05 MM")
      (fields (field (name "Comment") "RES-WR1"))
      (libsource (lib "*") (part "RES-WR1"))
    )
    (comp (ref "R27")
      (value "510R")
      (footprint "0603R")
      (description "WIRE WOUND RESISTOR 3.4 X 7.05 MM")
      (fields (field (name "Comment") "RES-WR1"))
      (libsource (lib "*") (part "RES-WR1"))
    )
    (comp (ref "R28")
      (value "510R")
      (footprint "0603R")
      (description "WIRE WOUND RESISTOR 3.4 X 7.05 MM")
      (fields (field (name "Comment") "RES-WR1"))
      (libsource (lib "*") (part "RES-WR1"))
    )
    (comp (ref "R29") (value "ROCKER") (footprint "ROCKER") (libsource (lib "*") (part "ROCKER")))
    (comp (ref "R30")
      (value "2K")
      (footprint "0603R")
      (description "WIRE WOUND RESISTOR 3.4 X 7.05 MM")
      (fields (field (name "Comment") "RES-WR1"))
      (libsource (lib "*") (part "RES-WR1"))
    )
    (comp (ref "R31") (value "ROCKER") (footprint "ROCKER") (libsource (lib "*") (part "ROCKER")))
    (comp (ref "R32")
      (value "2K")
      (footprint "0603R")
      (description "WIRE WOUND RESISTOR 3.4 X 7.05 MM")
      (fields (field (name "Comment") "RES-WR1"))
      (libsource (lib "*") (part "RES-WR1"))
    )
    (comp (ref "R33") (value "RK09K") (footprint "RK09K_RES") (libsource (lib "*") (part "RK09K")))
    (comp (ref "R40")
      (value "???")
      (footprint "0603R")
      (description "WIRE WOUND RESISTOR 3.4 X 7.05 MM")
      (fields (field (name "Comment") "RES-WR1"))
      (libsource (lib "*") (part "RES-WR1"))
    )
    (comp (ref "R51")
      (value "510R")
      (footprint "0603R")
      (description "WIRE WOUND RESISTOR 3.4 X 7.05 MM")
      (fields (field (name "Comment") "RES-WR1"))
      (libsource (lib "*") (part "RES-WR1"))
    )
    (comp (ref "R81")
      (value "???")
      (footprint "0603R")
      (description "WIRE WOUND RESISTOR 3.4 X 7.05 MM")
      (fields (field (name "Comment") "RES-WR1"))
      (libsource (lib "*") (part "RES-WR1"))
    )
    (comp (ref "R82")
      (value "???")
      (footprint "0603R")
      (description "WIRE WOUND RESISTOR 3.4 X 7.05 MM")
      (fields (field (name "Comment") "RES-WR1"))
      (libsource (lib "*") (part "RES-WR1"))
    )
    (comp (ref "R83")
      (value "???")
      (footprint "0603R")
      (description "WIRE WOUND RESISTOR 3.4 X 7.05 MM")
      (fields (field (name "Comment") "RES-WR1"))
      (libsource (lib "*") (part "RES-WR1"))
    )
    (comp (ref "R88")
      (value "510R")
      (footprint "0603R")
      (description "WIRE WOUND RESISTOR 3.4 X 7.05 MM")
      (fields (field (name "Comment") "RES-WR1"))
      (libsource (lib "*") (part "RES-WR1"))
    )
    (comp (ref "S1") (value "TOGGLE_SW") (footprint "TOGGLE_SWITCH") (libsource (lib "*") (part "TOGGLE_SW")))
    (comp (ref "S2") (value "TOGGLE_SW") (footprint "TOGGLE_SWITCH") (libsource (lib "*") (part "TOGGLE_SW")))
    (comp (ref "S3") (value "TOGGLE_SW") (footprint "TOGGLE_SWITCH") (libsource (lib "*") (part "TOGGLE_SW")))
    (comp (ref "S4") (value "TOGGLE_SW") (footprint "TOGGLE_SWITCH") (libsource (lib "*") (part "TOGGLE_SW")))
    (comp (ref "S5") (value "TOGGLE_SW") (footprint "TOGGLE_SWITCH") (libsource (lib "*") (part "TOGGLE_SW")))
    (comp (ref "S6") (value "TOGGLE_SW") (footprint "TOGGLE_SWITCH") (libsource (lib "*") (part "TOGGLE_SW")))
    (comp (ref "S7") (value "TOGGLE_SW") (footprint "TOGGLE_SWITCH") (libsource (lib "*") (part "TOGGLE_SW")))
    (comp (ref "S8") (value "TOGGLE_SW") (footprint "TOGGLE_SWITCH") (libsource (lib "*") (part "TOGGLE_SW")))
    (comp (ref "S9") (value "TOGGLE_SW") (footprint "TOGGLE_SWITCH") (libsource (lib "*") (part "TOGGLE_SW")))
    (comp (ref "S10")
      (value "TOGGLE_SW")
      (footprint "TOGGLE_SWITCH")
      (libsource (lib "*") (part "TOGGLE_SW"))
    )
    (comp (ref "S11")
      (value "TOGGLE_SW")
      (footprint "TOGGLE_SWITCH")
      (libsource (lib "*") (part "TOGGLE_SW"))
    )
    (comp (ref "S12")
      (value "TOGGLE_SW")
      (footprint "TOGGLE_SWITCH")
      (libsource (lib "*") (part "TOGGLE_SW"))
    )
    (comp (ref "U1")
      (value "DS0")
      (footprint "0805D")
      (fields (field (name "COMMENT_1") "LED"))
      (libsource (lib "*") (part "LED"))
    )
    (comp (ref "U2")
      (value "DS0")
      (footprint "0805D")
      (fields (field (name "COMMENT_1") "LED"))
      (libsource (lib "*") (part "LED"))
    )
    (comp (ref "U3")
      (value "STM32F103C")
      (footprint "LQFP-48_M")
      (description "STM32单片机48引脚")
      (libsource (lib "*") (part "STM32F103C"))
    )
    (comp (ref "U4")
      (value "DS0")
      (footprint "0805D")
      (fields (field (name "COMMENT_1") "LED"))
      (libsource (lib "*") (part "LED"))
    )
    (comp (ref "U5")
      (value "DS0")
      (footprint "0805D")
      (fields (field (name "COMMENT_1") "LED"))
      (libsource (lib "*") (part "LED"))
    )
    (comp (ref "U6")
      (value "DS0")
      (footprint "0805D")
      (fields (field (name "COMMENT_1") "LED"))
      (libsource (lib "*") (part "LED"))
    )
    (comp (ref "U7")
      (value "DS0")
      (footprint "0805D")
      (fields (field (name "COMMENT_1") "LED"))
      (libsource (lib "*") (part "LED"))
    )
    (comp (ref "U8")
      (value "DS0")
      (footprint "0805D")
      (fields (field (name "COMMENT_1") "LED"))
      (libsource (lib "*") (part "LED"))
    )
    (comp (ref "U9")
      (value "DS0")
      (footprint "0805D")
      (fields (field (name "COMMENT_1") "LED"))
      (libsource (lib "*") (part "LED"))
    )
    (comp (ref "U10")
      (value "DS0")
      (footprint "0805D")
      (fields (field (name "COMMENT_1") "LED"))
      (libsource (lib "*") (part "LED"))
    )
    (comp (ref "U11")
      (value "DS0")
      (footprint "0805D")
      (fields (field (name "COMMENT_1") "LED"))
      (libsource (lib "*") (part "LED"))
    )
    (comp (ref "U12")
      (value "DS0")
      (footprint "0805D")
      (fields (field (name "COMMENT_1") "LED"))
      (libsource (lib "*") (part "LED"))
    )
    (comp (ref "U13")
      (value "DS0")
      (footprint "0805D")
      (fields (field (name "COMMENT_1") "LED"))
      (libsource (lib "*") (part "LED"))
    )
    (comp (ref "U14")
      (value "DS0")
      (footprint "0805D")
      (fields (field (name "COMMENT_1") "LED"))
      (libsource (lib "*") (part "LED"))
    )
    (comp (ref "U15")
      (value "DS0")
      (footprint "0805D")
      (fields (field (name "COMMENT_1") "LED"))
      (libsource (lib "*") (part "LED"))
    )
    (comp (ref "U16")
      (value "DS0")
      (footprint "0805D")
      (fields (field (name "COMMENT_1") "LED"))
      (libsource (lib "*") (part "LED"))
    )
    (comp (ref "U17") (value "CH330") (footprint "SOP_8") (libsource (lib "*") (part "CH330")))
    (comp (ref "U18")
      (value "TPS737")
      (footprint "SOT-223-6_L6.5-W3.5-P1.27-BL")
      (libsource (lib "*") (part "TPS737"))
    )
    (comp (ref "U21")
      (value "DS0")
      (footprint "0805D")
      (fields (field (name "COMMENT_1") "LED"))
      (libsource (lib "*") (part "LED"))
    )
    (comp (ref "Y1") (value "XTAL") (footprint "XTAL3") (libsource (lib "PCB_Project1") (part "XTAL")))
    (comp (ref "Y6") (value "KEY") (footprint "KEY_3_6_2.5") (libsource (lib "*") (part "KEY")))
  )
  (nets
    (net (code "1") (name "+5V") (class "Default")
      (node (ref "C1") (pin "2") (pinfunction "2_2") (pintype "passive"))
      (node (ref "C15") (pin "2") (pinfunction "2_2") (pintype "passive"))
      (node (ref "C16") (pin "2") (pinfunction "2_2") (pintype "passive"))
      (node (ref "C43") (pin "2") (pinfunction "2_2") (pintype "passive"))
      (node (ref "C44") (pin "2") (pinfunction "2_2") (pintype "passive"))
      (node (ref "C45") (pin "2") (pinfunction "2_2") (pintype "passive"))
      (node (ref "J1") (pin "1") (pinfunction "VCC_1") (pintype "passive"))
      (node (ref "U17") (pin "5") (pinfunction "VCC_5") (pintype "passive"))
      (node (ref "U18") (pin "1") (pinfunction "IN_1") (pintype "passive"))
      (node (ref "U18") (pin "5") (pinfunction "EN_5") (pintype "passive"))
    )
    (net (code "2") (name "/ADC1") (class "Default")
      (node (ref "C20") (pin "2") (pinfunction "2_2") (pintype "passive"))
      (node (ref "R29") (pin "2") (pinfunction "2_2") (pintype "passive"))
      (node (ref "U3") (pin "10") (pinfunction "PA0/WKUP/ADC123_IN0/T2C1ETR/T5C1/T8ETR_10") (pintype "passive"))
    )
    (net (code "3") (name "/ADC2") (class "Default")
      (node (ref "R29") (pin "5") (pinfunction "5_5") (pintype "passive"))
      (node (ref "R30") (pin "2") (pinfunction "2_2") (pintype "passive"))
      (node (ref "U3") (pin "11") (pinfunction "PA1/ADC123_IN1/T5C2/T2C2_11") (pintype "passive"))
    )
    (net (code "4") (name "/ADC3") (class "Default")
      (node (ref "C21") (pin "2") (pinfunction "2_2") (pintype "passive"))
      (node (ref "R29") (pin "7") (pinfunction "7_7") (pintype "passive"))
      (node (ref "U3") (pin "12") (pinfunction "PA2/ADC123_IN2/USART2_TX/T5C3/T2C3_12") (pintype "passive"))
    )
    (net (code "5") (name "/ADC4") (class "Default")
      (node (ref "C22") (pin "2") (pinfunction "2_2") (pintype "passive"))
      (node (ref "R29") (pin "10") (pinfunction "10_10") (pintype "passive"))
      (node (ref "U3") (pin "13") (pinfunction "PA3/ADC123_IN3/USART2_RX/T5C4/T2C4_13") (pintype "passive"))
    )
    (net (code "6") (name "/ADC5") (class "Default")
      (node (ref "C23") (pin "2") (pinfunction "2_2") (pintype "passive"))
      (node (ref "R31") (pin "2") (pinfunction "2_2") (pintype "passive"))
      (node (ref "U3") (pin "14") (pinfunction "PA4/ADC123_IN4/DAC_OUT1/SPI1_NSS_14") (pintype "passive"))
    )
    (net (code "7") (name "/ADC6") (class "Default")
      (node (ref "R31") (pin "5") (pinfunction "5_5") (pintype "passive"))
      (node (ref "R32") (pin "2") (pinfunction "2_2") (pintype "passive"))
      (node (ref "U3") (pin "15") (pinfunction "PA5/ADC123_IN5/DAC_OUT2/SPI1_SCK_15") (pintype "passive"))
    )
    (net (code "8") (name "/ADC7") (class "Default")
      (node (ref "C24") (pin "2") (pinfunction "2_2") (pintype "passive"))
      (node (ref "R31") (pin "7") (pinfunction "7_7") (pintype "passive"))
      (node (ref "U3") (pin "16") (pinfunction "PA6/ADC123_IN6/SPI1_MISO/T8T1BKIN/T3C1_16") (pintype "passive"))
    )
    (net (code "9") (name "/ADC8") (class "Default")
      (node (ref "C25") (pin "2") (pinfunction "2_2") (pintype "passive"))
      (node (ref "R31") (pin "10") (pinfunction "10_10") (pintype "passive"))
      (node (ref "U3") (pin "17") (pinfunction "PA7/ADC123_IN7/SPI1_MOSI/T8C1N/T3C2/T1C1_17") (pintype "passive"))
    )
    (net (code "10") (name "/ADC9") (class "Default")
      (node (ref "C28") (pin "1") (pinfunction "1_1") (pintype "passive"))
      (node (ref "R33") (pin "2") (pinfunction "2_2") (pintype "passive"))
      (node (ref "U3") (pin "18") (pinfunction "PB0/ADC123_IN8/T3C3/T8C2N/T1C2N_18") (pintype "passive"))
    )
    (net (code "11") (name "/ADC10") (class "Default")
      (node (ref "U3") (pin "19") (pinfunction "PB1/ADC123_IN9/T3C4/T8C3N/T1C3N_19") (pintype "passive"))
    )
    (net (code "12") (name "/BOOT0") (class "Default")
      (node (ref "R40") (pin "1") (pinfunction "1_1") (pintype "passive"))
      (node (ref "R82") (pin "2") (pinfunction "2_2") (pintype "passive"))
      (node (ref "U3") (pin "44") (pinfunction "BOOT0_44") (pintype "passive"))
    )
    (net (code "13") (name "/BOOT1") (class "Default")
      (node (ref "R81") (pin "1") (pinfunction "1_1") (pintype "passive"))
      (node (ref "R83") (pin "2") (pinfunction "2_2") (pintype "passive"))
      (node (ref "U3") (pin "20") (pinfunction "PB2/BOOT1_20") (pintype "passive"))
    )
    (net (code "14") (name "/CH330_D+") (class "Default")
      (node (ref "J1") (pin "3") (pinfunction "D+_3") (pintype "passive"))
      (node (ref "U17") (pin "1") (pinfunction "UD+_1") (pintype "passive"))
    )
    (net (code "15") (name "/CH330_D-") (class "Default")
      (node (ref "J1") (pin "2") (pinfunction "D-_2") (pintype "passive"))
      (node (ref "U17") (pin "2") (pinfunction "UD-_2") (pintype "passive"))
    )
    (net (code "16") (name "/LED0") (class "Default")
      (node (ref "U14") (pin "2") (pinfunction "2_2") (pintype "passive"))
      (node (ref "U3") (pin "2") (pinfunction "PC13-TAMPER-RTC_2") (pintype "passive"))
    )
    (net (code "17") (name "/LED1") (class "Default")
      (node (ref "U15") (pin "2") (pinfunction "2_2") (pintype "passive"))
      (node (ref "U3") (pin "3") (pinfunction "PC14-OSC32_IN_3") (pintype "passive"))
    )
    (net (code "18") (name "/LED2") (class "Default")
      (node (ref "U16") (pin "2") (pinfunction "2_2") (pintype "passive"))
      (node (ref "U3") (pin "4") (pinfunction "PC15-OSC32_OUT_4") (pintype "passive"))
    )
    (net (code "19") (name "/NRST") (class "Default")
      (node (ref "C108") (pin "1") (pinfunction "1_1") (pintype "passive"))
      (node (ref "U3") (pin "7") (pinfunction "NRST_7") (pintype "passive"))
      (node (ref "Y6") (pin "1") (pinfunction "1_1") (pintype "passive"))
    )
    (net (code "20") (name "/OSCIN") (class "Default")
      (node (ref "C26") (pin "2") (pinfunction "2_2") (pintype "passive"))
      (node (ref "U3") (pin "5") (pinfunction "OSC_IN_5") (pintype "passive"))
      (node (ref "Y1") (pin "2") (pinfunction "2_2") (pintype "passive"))
    )
    (net (code "21") (name "/OSCOUT") (class "Default")
      (node (ref "C27") (pin "2") (pinfunction "2_2") (pintype "passive"))
      (node (ref "U3") (pin "6") (pinfunction "OSC_OUT_6") (pintype "passive"))
      (node (ref "Y1") (pin "1") (pinfunction "1_1") (pintype "passive"))
    )
    (net (code "22") (name "/PA11") (class "Default")
      (node (ref "P1") (pin "4") (pinfunction "4_4") (pintype "passive"))
      (node (ref "U3") (pin "32") (pinfunction "PA11/CAN_RX/T1C4/USBDM_32") (pintype "passive"))
    )
    (net (code "23") (name "/PA12") (class "Default")
      (node (ref "P1") (pin "3") (pinfunction "3_3") (pintype "passive"))
      (node (ref "U3") (pin "33") (pinfunction "PA12/CAN_TX/T1ETR/USBDP_33") (pintype "passive"))
    )
    (net (code "24") (name "/PB3") (class "Default")
      (node (ref "C3") (pin "1") (pinfunction "1_1") (pintype "passive"))
      (node (ref "R1") (pin "2") (pinfunction "2_2") (pintype "passive"))
      (node (ref "R2") (pin "2") (pinfunction "2_2") (pintype "passive"))
      (node (ref "S1") (pin "2") (pinfunction "2_2") (pintype "passive"))
      (node (ref "U3") (pin "39") (pinfunction "PB3/JTDO/SPI3_SCK/I2S3_CK/T2C2/SPI1_SCK_39") (pintype "passive"))
    )
    (net (code "25") (name "/PB4") (class "Default")
      (node (ref "C4") (pin "1") (pinfunction "1_1") (pintype "passive"))
      (node (ref "R3") (pin "2") (pinfunction "2_2") (pintype "passive"))
      (node (ref "R4") (pin "2") (pinfunction "2_2") (pintype "passive"))
      (node (ref "S2") (pin "2") (pinfunction "2_2") (pintype "passive"))
      (node (ref "U3") (pin "40") (pinfunction "PB4/NJTRST/SPI3_MISO/T3C1/SPI1_MISO_40") (pintype "passive"))
    )
    (net (code "26") (name "/PB5") (class "Default")
      (node (ref "C5") (pin "1") (pinfunction "1_1") (pintype "passive"))
      (node (ref "R5") (pin "2") (pinfunction "2_2") (pintype "passive"))
      (node (ref "R6") (pin "2") (pinfunction "2_2") (pintype "passive"))
      (node (ref "S3") (pin "2") (pinfunction "2_2") (pintype "passive"))
      (node (ref "U3") (pin "41") (pinfunction "PB5/I2C1_SMBA/I2S3_SD/SPI3_MOSI/T3C2/SPI_41") (pintype "passive"))
    )
    (net (code "27") (name "/PB6") (class "Default")
      (node (ref "C6") (pin "1") (pinfunction "1_1") (pintype "passive"))
      (node (ref "R7") (pin "2") (pinfunction "2_2") (pintype "passive"))
      (node (ref "R8") (pin "2") (pinfunction "2_2") (pintype "passive"))
      (node (ref "S4") (pin "2") (pinfunction "2_2") (pintype "passive"))
      (node (ref "U3") (pin "42") (pinfunction "PB6/I2C1_SCL/T4C1/USART1_TX_42") (pintype "passive"))
    )
    (net (code "28") (name "/PB7") (class "Default")
      (node (ref "C7") (pin "1") (pinfunction "1_1") (pintype "passive"))
      (node (ref "R10") (pin "2") (pinfunction "2_2") (pintype "passive"))
      (node (ref "R9") (pin "2") (pinfunction "2_2") (pintype "passive"))
      (node (ref "S5") (pin "2") (pinfunction "2_2") (pintype "passive"))
      (node (ref "U3") (pin "43") (pinfunction "PB7/I2C1_SDA/FSMC_NADV/USART1_RX_43") (pintype "passive"))
    )
    (net (code "29") (name "/PB8") (class "Default")
      (node (ref "C8") (pin "1") (pinfunction "1_1") (pintype "passive"))
      (node (ref "R11") (pin "2") (pinfunction "2_2") (pintype "passive"))
      (node (ref "R12") (pin "2") (pinfunction "2_2") (pintype "passive"))
      (node (ref "S6") (pin "2") (pinfunction "2_2") (pintype "passive"))
      (node (ref "U3") (pin "45") (pinfunction "PB8/SDIO_D4/I2C1_SCL/T4C3(7)/CAN_RX_45") (pintype "passive"))
    )
    (net (code "30") (name "/PB9") (class "Default")
      (node (ref "C9") (pin "1") (pinfunction "1_1") (pintype "passive"))
      (node (ref "R13") (pin "2") (pinfunction "2_2") (pintype "passive"))
      (node (ref "R14") (pin "2") (pinfunction "2_2") (pintype "passive"))
      (node (ref "S7") (pin "2") (pinfunction "2_2") (pintype "passive"))
      (node (ref "U3") (pin "46") (pinfunction "PB9/SDIO_D5/I2C1_SDA/T4C4/CAN_TX_46") (pintype "passive"))
    )
    (net (code "31") (name "/PB10") (class "Default")
      (node (ref "C10") (pin "1") (pinfunction "1_1") (pintype "passive"))
      (node (ref "R15") (pin "2") (pinfunction "2_2") (pintype "passive"))
      (node (ref "R16") (pin "2") (pinfunction "2_2") (pintype "passive"))
      (node (ref "S8") (pin "2") (pinfunction "2_2") (pintype "passive"))
      (node (ref "U3") (pin "21") (pinfunction "PB10/USART3_TX/I2C2_SCL/T2C3_21") (pintype "passive"))
    )
    (net (code "32") (name "/PB11") (class "Default")
      (node (ref "C11") (pin "1") (pinfunction "1_1") (pintype "passive"))
      (node (ref "R17") (pin "2") (pinfunction "2_2") (pintype "passive"))
      (node (ref "R18") (pin "2") (pinfunction "2_2") (pintype "passive"))
      (node (ref "S9") (pin "2") (pinfunction "2_2") (pintype "passive"))
      (node (ref "U3") (pin "22") (pinfunction "PB11/USART3_RX/I2C2_SDA/T2C4_22") (pintype "passive"))
    )
    (net (code "33") (name "/PB12") (class "Default")
      (node (ref "C12") (pin "1") (pinfunction "1_1") (pintype "passive"))
      (node (ref "R19") (pin "2") (pinfunction "2_2") (pintype "passive"))
      (node (ref "R20") (pin "2") (pinfunction "2_2") (pintype "passive"))
      (node (ref "S10") (pin "2") (pinfunction "2_2") (pintype "passive"))
      (node (ref "U3") (pin "25") (pinfunction "PB12/I2S2_WS/T1BKIN/SPI2_NSS/I2C2_SMBA_25") (pintype "passive"))
    )
    (net (code "34") (name "/PB13") (class "Default")
      (node (ref "C13") (pin "1") (pinfunction "1_1") (pintype "passive"))
      (node (ref "R21") (pin "2") (pinfunction "2_2") (pintype "passive"))
      (node (ref "R22") (pin "2") (pinfunction "2_2") (pintype "passive"))
      (node (ref "S11") (pin "2") (pinfunction "2_2") (pintype "passive"))
      (node (ref "U3") (pin "26") (pinfunction "PB13/I2S2_CK/T1CH1N/SPI2_SCK_26") (pintype "passive"))
    )
    (net (code "35") (name "/PB14") (class "Default")
      (node (ref "C14") (pin "1") (pinfunction "1_1") (pintype "passive"))
      (node (ref "R23") (pin "2") (pinfunction "2_2") (pintype "passive"))
      (node (ref "R24") (pin "2") (pinfunction "2_2") (pintype "passive"))
      (node (ref "S12") (pin "2") (pinfunction "2_2") (pintype "passive"))
      (node (ref "U3") (pin "27") (pinfunction "PB14/T1CH2N/SPI2_MISO_27") (pintype "passive"))
    )
    (net (code "36") (name "/SWCLK") (class "Default")
      (node (ref "P4") (pin "2") (pinfunction "2_2") (pintype "passive"))
      (node (ref "U3") (pin "37") (pinfunction "PA14/JTCK/SWCLK_37") (pintype "passive"))
    )
    (net (code "37") (name "/SWIO") (class "Default")
      (node (ref "P4") (pin "3") (pinfunction "3_3") (pintype "passive"))
      (node (ref "U3") (pin "34") (pinfunction "PA13/JTMS/SWDIO_34") (pintype "passive"))
    )
    (net (code "38") (name "/U1_RX") (class "Default")
      (node (ref "P2") (pin "2") (pinfunction "2_2") (pintype "passive"))
      (node (ref "U17") (pin "6") (pinfunction "TXD_6") (pintype "passive"))
      (node (ref "U3") (pin "31") (pinfunction "PA10/T1C3/USART1_RX_31") (pintype "passive"))
    )
    (net (code "39") (name "/U1_TX") (class "Default")
      (node (ref "P2") (pin "3") (pinfunction "3_3") (pintype "passive"))
      (node (ref "U17") (pin "7") (pinfunction "RXD_7") (pintype "passive"))
      (node (ref "U3") (pin "30") (pinfunction "PA9/T1C2/USART1_TX_30") (pintype "passive"))
    )
    (net (code "40") (name "AGND") (class "Default")
      (node (ref "C1") (pin "1") (pinfunction "1_1") (pintype "passive"))
      (node (ref "C10") (pin "2") (pinfunction "2_2") (pintype "passive"))
      (node (ref "C102") (pin "2") (pinfunction "2_2") (pintype "passive"))
      (node (ref "C103") (pin "2") (pinfunction "2_2") (pintype "passive"))
      (node (ref "C104") (pin "2") (pinfunction "2_2") (pintype "passive"))
      (node (ref "C108") (pin "2") (pinfunction "2_2") (pintype "passive"))
      (node (ref "C11") (pin "2") (pinfunction "2_2") (pintype "passive"))
      (node (ref "C12") (pin "2") (pinfunction "2_2") (pintype "passive"))
      (node (ref "C13") (pin "2") (pinfunction "2_2") (pintype "passive"))
      (node (ref "C14") (pin "2") (pinfunction "2_2") (pintype "passive"))
      (node (ref "C15") (pin "1") (pinfunction "1_1") (pintype "passive"))
      (node (ref "C16") (pin "1") (pinfunction "1_1") (pintype "passive"))
      (node (ref "C17") (pin "2") (pinfunction "2_2") (pintype "passive"))
      (node (ref "C18") (pin "1") (pinfunction "1_1") (pintype "passive"))
      (node (ref "C19") (pin "1") (pinfunction "1_1") (pintype "passive"))
      (node (ref "C2") (pin "1") (pinfunction "1_1") (pintype "passive"))
      (node (ref "C26") (pin "1") (pinfunction "1_1") (pintype "passive"))
      (node (ref "C27") (pin "1") (pinfunction "1_1") (pintype "passive"))
      (node (ref "C28") (pin "2") (pinfunction "2_2") (pintype "passive"))
      (node (ref "C3") (pin "2") (pinfunction "2_2") (pintype "passive"))
      (node (ref "C30") (pin "1") (pinfunction "1_1") (pintype "passive"))
      (node (ref "C4") (pin "2") (pinfunction "2_2") (pintype "passive"))
      (node (ref "C43") (pin "1") (pinfunction "1_1") (pintype "passive"))
      (node (ref "C44") (pin "1") (pinfunction "1_1") (pintype "passive"))
      (node (ref "C45") (pin "1") (pinfunction "1_1") (pintype "passive"))
      (node (ref "C46") (pin "1") (pinfunction "1_1") (pintype "passive"))
      (node (ref "C47") (pin "1") (pinfunction "1_1") (pintype "passive"))
      (node (ref "C48") (pin "1") (pinfunction "1_1") (pintype "passive"))
      (node (ref "C49") (pin "1") (pinfunction "1_1") (pintype "passive"))
      (node (ref "C5") (pin "2") (pinfunction "2_2") (pintype "passive"))
      (node (ref "C6") (pin "2") (pinfunction "2_2") (pintype "passive"))
      (node (ref "C66") (pin "2") (pinfunction "2_2") (pintype "passive"))
      (node (ref "C67") (pin "2") (pinfunction "2_2") (pintype "passive"))
      (node (ref "C68") (pin "2") (pinfunction "2_2") (pintype "passive"))
      (node (ref "C69") (pin "2") (pinfunction "2_2") (pintype "passive"))
      (node (ref "C7") (pin "2") (pinfunction "2_2") (pintype "passive"))
      (node (ref "C70") (pin "2") (pinfunction "2_2") (pintype "passive"))
      (node (ref "C71") (pin "2") (pinfunction "2_2") (pintype "passive"))
      (node (ref "C72") (pin "2") (pinfunction "2_2") (pintype "passive"))
      (node (ref "C73") (pin "2") (pinfunction "2_2") (pintype "passive"))
      (node (ref "C8") (pin "2") (pinfunction "2_2") (pintype "passive"))
      (node (ref "C9") (pin "2") (pinfunction "2_2") (pintype "passive"))
      (node (ref "J1") (pin "5") (pinfunction "GND_5") (pintype "passive"))
      (node (ref "P1") (pin "1") (pinfunction "1_1") (pintype "passive"))
      (node (ref "P2") (pin "1") (pinfunction "1_1") (pintype "passive"))
      (node (ref "P4") (pin "1") (pinfunction "1_1") (pintype "passive"))
      (node (ref "R10") (pin "1") (pinfunction "1_1") (pintype "passive"))
      (node (ref "R12") (pin "1") (pinfunction "1_1") (pintype "passive"))
      (node (ref "R14") (pin "1") (pinfunction "1_1") (pintype "passive"))
      (node (ref "R16") (pin "1") (pinfunction "1_1") (pintype "passive"))
      (node (ref "R18") (pin "1") (pinfunction "1_1") (pintype "passive"))
      (node (ref "R2") (pin "1") (pinfunction "1_1") (pintype "passive"))
      (node (ref "R20") (pin "1") (pinfunction "1_1") (pintype "passive"))
      (node (ref "R22") (pin "1") (pinfunction "1_1") (pintype "passive"))
      (node (ref "R24") (pin "1") (pinfunction "1_1") (pintype "passive"))
      (node (ref "R29") (pin "11") (pinfunction "11_11") (pintype "passive"))
      (node (ref "R29") (pin "3") (pinfunction "3_3") (pintype "passive"))
      (node (ref "R29") (pin "6") (pinfunction "6_6") (pintype "passive"))
      (node (ref "R30") (pin "1") (pinfunction "1_1") (pintype "passive"))
      (node (ref "R31") (pin "11") (pinfunction "11_11") (pintype "passive"))
      (node (ref "R31") (pin "3") (pinfunction "3_3") (pintype "passive"))
      (node (ref "R31") (pin "6") (pinfunction "6_6") (pintype "passive"))
      (node (ref "R32") (pin "1") (pinfunction "1_1") (pintype "passive"))
      (node (ref "R33") (pin "3") (pinfunction "3_3") (pintype "passive"))
      (node (ref "R4") (pin "1") (pinfunction "1_1") (pintype "passive"))
      (node (ref "R6") (pin "1") (pinfunction "1_1") (pintype "passive"))
      (node (ref "R8") (pin "1") (pinfunction "1_1") (pintype "passive"))
      (node (ref "R82") (pin "1") (pinfunction "1_1") (pintype "passive"))
      (node (ref "R83") (pin "1") (pinfunction "1_1") (pintype "passive"))
      (node (ref "R88") (pin "2") (pinfunction "2_2") (pintype "passive"))
      (node (ref "U1") (pin "2") (pinfunction "2_2") (pintype "passive"))
      (node (ref "U10") (pin "2") (pinfunction "2_2") (pintype "passive"))
      (node (ref "U11") (pin "2") (pinfunction "2_2") (pintype "passive"))
      (node (ref "U12") (pin "2") (pinfunction "2_2") (pintype "passive"))
      (node (ref "U13") (pin "2") (pinfunction "2_2") (pintype "passive"))
      (node (ref "U17") (pin "3") (pinfunction "GND_3") (pintype "passive"))
      (node (ref "U18") (pin "3") (pinfunction "GND_3") (pintype "passive"))
      (node (ref "U18") (pin "6") (pinfunction "GND_6") (pintype "passive"))
      (node (ref "U2") (pin "2") (pinfunction "2_2") (pintype "passive"))
      (node (ref "U21") (pin "2") (pinfunction "2_2") (pintype "passive"))
      (node (ref "U3") (pin "23") (pinfunction "VSS_1_23") (pintype "passive"))
      (node (ref "U3") (pin "35") (pinfunction "VSS_2_35") (pintype "passive"))
      (node (ref "U3") (pin "47") (pinfunction "VSS_3_47") (pintype "passive"))
      (node (ref "U3") (pin "8") (pinfunction "VSSA_8") (pintype "passive"))
      (node (ref "U4") (pin "2") (pinfunction "2_2") (pintype "passive"))
      (node (ref "U5") (pin "2") (pinfunction "2_2") (pintype "passive"))
      (node (ref "U6") (pin "2") (pinfunction "2_2") (pintype "passive"))
      (node (ref "U7") (pin "2") (pinfunction "2_2") (pintype "passive"))
      (node (ref "U8") (pin "2") (pinfunction "2_2") (pintype "passive"))
      (node (ref "U9") (pin "2") (pinfunction "2_2") (pintype "passive"))
      (node (ref "Y1") (pin "3") (pinfunction "3_3") (pintype "passive"))
      (node (ref "Y1") (pin "4") (pinfunction "4_4") (pintype "passive"))
      (node (ref "Y6") (pin "2") (pinfunction "2_2") (pintype "passive"))
    )
    (net (code "41") (name "Net-(R1-Pad1)") (class "Default")
      (node (ref "R1") (pin "1") (pinfunction "1_1") (pintype "passive"))
      (node (ref "U21") (pin "1") (pinfunction "1_1") (pintype "passive"))
    )
    (net (code "42") (name "Net-(R3-Pad1)") (class "Default")
      (node (ref "R3") (pin "1") (pinfunction "1_1") (pintype "passive"))
      (node (ref "U1") (pin "1") (pinfunction "1_1") (pintype "passive"))
    )
    (net (code "43") (name "Net-(R5-Pad1)") (class "Default")
      (node (ref "R5") (pin "1") (pinfunction "1_1") (pintype "passive"))
      (node (ref "U2") (pin "1") (pinfunction "1_1") (pintype "passive"))
    )
    (net (code "44") (name "Net-(R7-Pad1)") (class "Default")
      (node (ref "R7") (pin "1") (pinfunction "1_1") (pintype "passive"))
      (node (ref "U4") (pin "1") (pinfunction "1_1") (pintype "passive"))
    )
    (net (code "45") (name "Net-(R9-Pad1)") (class "Default")
      (node (ref "R9") (pin "1") (pinfunction "1_1") (pintype "passive"))
      (node (ref "U5") (pin "1") (pinfunction "1_1") (pintype "passive"))
    )
    (net (code "46") (name "Net-(R11-Pad1)") (class "Default")
      (node (ref "R11") (pin "1") (pinfunction "1_1") (pintype "passive"))
      (node (ref "U6") (pin "1") (pinfunction "1_1") (pintype "passive"))
    )
    (net (code "47") (name "Net-(R13-Pad1)") (class "Default")
      (node (ref "R13") (pin "1") (pinfunction "1_1") (pintype "passive"))
      (node (ref "U7") (pin "1") (pinfunction "1_1") (pintype "passive"))
    )
    (net (code "48") (name "Net-(R15-Pad1)") (class "Default")
      (node (ref "R15") (pin "1") (pinfunction "1_1") (pintype "passive"))
      (node (ref "U8") (pin "1") (pinfunction "1_1") (pintype "passive"))
    )
    (net (code "49") (name "Net-(R17-Pad1)") (class "Default")
      (node (ref "R17") (pin "1") (pinfunction "1_1") (pintype "passive"))
      (node (ref "U9") (pin "1") (pinfunction "1_1") (pintype "passive"))
    )
    (net (code "50") (name "Net-(R19-Pad1)") (class "Default")
      (node (ref "R19") (pin "1") (pinfunction "1_1") (pintype "passive"))
      (node (ref "U10") (pin "1") (pinfunction "1_1") (pintype "passive"))
    )
    (net (code "51") (name "Net-(R21-Pad1)") (class "Default")
      (node (ref "R21") (pin "1") (pinfunction "1_1") (pintype "passive"))
      (node (ref "U11") (pin "1") (pinfunction "1_1") (pintype "passive"))
    )
    (net (code "52") (name "Net-(R23-Pad1)") (class "Default")
      (node (ref "R23") (pin "1") (pinfunction "1_1") (pintype "passive"))
      (node (ref "U12") (pin "1") (pinfunction "1_1") (pintype "passive"))
    )
    (net (code "53") (name "Net-(R25-Pad2)") (class "Default")
      (node (ref "R25") (pin "2") (pinfunction "2_2") (pintype "passive"))
      (node (ref "U13") (pin "1") (pinfunction "1_1") (pintype "passive"))
    )
    (net (code "54") (name "Net-(R26-Pad2)") (class "Default")
      (node (ref "R26") (pin "2") (pinfunction "2_2") (pintype "passive"))
      (node (ref "U14") (pin "1") (pinfunction "1_1") (pintype "passive"))
    )
    (net (code "55") (name "Net-(R27-Pad2)") (class "Default")
      (node (ref "R27") (pin "2") (pinfunction "2_2") (pintype "passive"))
      (node (ref "U15") (pin "1") (pinfunction "1_1") (pintype "passive"))
    )
    (net (code "56") (name "Net-(R28-Pad2)") (class "Default")
      (node (ref "R28") (pin "2") (pinfunction "2_2") (pintype "passive"))
      (node (ref "U16") (pin "1") (pinfunction "1_1") (pintype "passive"))
    )
    (net (code "57") (name "Net-(U17-V3)") (class "Default")
      (node (ref "C17") (pin "1") (pinfunction "1_1") (pintype "passive"))
      (node (ref "U17") (pin "8") (pinfunction "V3_8") (pintype "passive"))
    )
    (net (code "58") (name "Net-(U18-FB)") (class "Default")
      (node (ref "R51") (pin "2") (pinfunction "2_2") (pintype "passive"))
      (node (ref "R88") (pin "1") (pinfunction "1_1") (pintype "passive"))
      (node (ref "U18") (pin "4") (pinfunction "FB_4") (pintype "passive"))
    )
    (net (code "59") (name "VCC_3.3V") (class "Default")
      (node (ref "C102") (pin "1") (pinfunction "1_1") (pintype "passive"))
      (node (ref "C103") (pin "1") (pinfunction "1_1") (pintype "passive"))
      (node (ref "C104") (pin "1") (pinfunction "1_1") (pintype "passive"))
      (node (ref "C18") (pin "2") (pinfunction "2_2") (pintype "passive"))
      (node (ref "C19") (pin "2") (pinfunction "2_2") (pintype "passive"))
      (node (ref "C2") (pin "2") (pinfunction "2_2") (pintype "passive"))
      (node (ref "C20") (pin "1") (pinfunction "1_1") (pintype "passive"))
      (node (ref "C21") (pin "1") (pinfunction "1_1") (pintype "passive"))
      (node (ref "C22") (pin "1") (pinfunction "1_1") (pintype "passive"))
      (node (ref "C23") (pin "1") (pinfunction "1_1") (pintype "passive"))
      (node (ref "C24") (pin "1") (pinfunction "1_1") (pintype "passive"))
      (node (ref "C25") (pin "1") (pinfunction "1_1") (pintype "passive"))
      (node (ref "C30") (pin "2") (pinfunction "2_2") (pintype "passive"))
      (node (ref "C46") (pin "2") (pinfunction "2_2") (pintype "passive"))
      (node (ref "C47") (pin "2") (pinfunction "2_2") (pintype "passive"))
      (node (ref "C48") (pin "2") (pinfunction "2_2") (pintype "passive"))
      (node (ref "C49") (pin "2") (pinfunction "2_2") (pintype "passive"))
      (node (ref "C66") (pin "1") (pinfunction "1_1") (pintype "passive"))
      (node (ref "C67") (pin "1") (pinfunction "1_1") (pintype "passive"))
      (node (ref "C68") (pin "1") (pinfunction "1_1") (pintype "passive"))
      (node (ref "C69") (pin "1") (pinfunction "1_1") (pintype "passive"))
      (node (ref "C70") (pin "1") (pinfunction "1_1") (pintype "passive"))
      (node (ref "C71") (pin "1") (pinfunction "1_1") (pintype "passive"))
      (node (ref "C72") (pin "1") (pinfunction "1_1") (pintype "passive"))
      (node (ref "C73") (pin "1") (pinfunction "1_1") (pintype "passive"))
      (node (ref "P1") (pin "2") (pinfunction "2_2") (pintype "passive"))
      (node (ref "P2") (pin "4") (pinfunction "4_4") (pintype "passive"))
      (node (ref "P4") (pin "4") (pinfunction "4_4") (pintype "passive"))
      (node (ref "R25") (pin "1") (pinfunction "1_1") (pintype "passive"))
      (node (ref "R26") (pin "1") (pinfunction "1_1") (pintype "passive"))
      (node (ref "R27") (pin "1") (pinfunction "1_1") (pintype "passive"))
      (node (ref "R28") (pin "1") (pinfunction "1_1") (pintype "passive"))
      (node (ref "R29") (pin "1") (pinfunction "1_1") (pintype "passive"))
      (node (ref "R29") (pin "4") (pinfunction "4_4") (pintype "passive"))
      (node (ref "R29") (pin "8") (pinfunction "8_8") (pintype "passive"))
      (node (ref "R29") (pin "9") (pinfunction "9_9") (pintype "passive"))
      (node (ref "R31") (pin "1") (pinfunction "1_1") (pintype "passive"))
      (node (ref "R31") (pin "4") (pinfunction "4_4") (pintype "passive"))
      (node (ref "R31") (pin "8") (pinfunction "8_8") (pintype "passive"))
      (node (ref "R31") (pin "9") (pinfunction "9_9") (pintype "passive"))
      (node (ref "R33") (pin "1") (pinfunction "1_1") (pintype "passive"))
      (node (ref "R40") (pin "2") (pinfunction "2_2") (pintype "passive"))
      (node (ref "R51") (pin "1") (pinfunction "1_1") (pintype "passive"))
      (node (ref "R81") (pin "2") (pinfunction "2_2") (pintype "passive"))
      (node (ref "S1") (pin "3") (pinfunction "3_3") (pintype "passive"))
      (node (ref "S10") (pin "3") (pinfunction "3_3") (pintype "passive"))
      (node (ref "S11") (pin "3") (pinfunction "3_3") (pintype "passive"))
      (node (ref "S12") (pin "3") (pinfunction "3_3") (pintype "passive"))
      (node (ref "S2") (pin "3") (pinfunction "3_3") (pintype "passive"))
      (node (ref "S3") (pin "3") (pinfunction "3_3") (pintype "passive"))
      (node (ref "S4") (pin "3") (pinfunction "3_3") (pintype "passive"))
      (node (ref "S5") (pin "3") (pinfunction "3_3") (pintype "passive"))
      (node (ref "S6") (pin "3") (pinfunction "3_3") (pintype "passive"))
      (node (ref "S7") (pin "3") (pinfunction "3_3") (pintype "passive"))
      (node (ref "S8") (pin "3") (pinfunction "3_3") (pintype "passive"))
      (node (ref "S9") (pin "3") (pinfunction "3_3") (pintype "passive"))
      (node (ref "U18") (pin "2") (pinfunction "OUT_2") (pintype "passive"))
      (node (ref "U3") (pin "24") (pinfunction "VDD_1_24") (pintype "passive"))
      (node (ref "U3") (pin "36") (pinfunction "VDD_2_36") (pintype "passive"))
      (node (ref "U3") (pin "48") (pinfunction "VDD_3_48") (pintype "passive"))
      (node (ref "U3") (pin "9") (pinfunction "VDDA_9") (pintype "passive"))
    )
    (net (code "60") (name "unconnected-(J1-EP-Pad6)") (class "Default")
      (node (ref "J1") (pin "6") (pinfunction "EP_6") (pintype "passive"))
    )
    (net (code "61") (name "unconnected-(J1-EP-Pad7)") (class "Default")
      (node (ref "J1") (pin "7") (pinfunction "EP_7") (pintype "passive"))
    )
    (net (code "62") (name "unconnected-(J1-ID-Pad4)") (class "Default")
      (node (ref "J1") (pin "4") (pinfunction "ID_4") (pintype "passive"))
    )
    (net (code "63") (name "unconnected-(R33-Pad4)") (class "Default")
      (node (ref "R33") (pin "4") (pinfunction "4_4") (pintype "passive"))
    )
    (net (code "64") (name "unconnected-(R33-Pad5)") (class "Default")
      (node (ref "R33") (pin "5") (pinfunction "5_5") (pintype "passive"))
    )
    (net (code "65") (name "unconnected-(S1-Pad1)") (class "Default")
      (node (ref "S1") (pin "1") (pinfunction "1_1") (pintype "passive"))
    )
    (net (code "66") (name "unconnected-(S2-Pad1)") (class "Default")
      (node (ref "S2") (pin "1") (pinfunction "1_1") (pintype "passive"))
    )
    (net (code "67") (name "unconnected-(S3-Pad1)") (class "Default")
      (node (ref "S3") (pin "1") (pinfunction "1_1") (pintype "passive"))
    )
    (net (code "68") (name "unconnected-(S4-Pad1)") (class "Default")
      (node (ref "S4") (pin "1") (pinfunction "1_1") (pintype "passive"))
    )
    (net (code "69") (name "unconnected-(S5-Pad1)") (class "Default")
      (node (ref "S5") (pin "1") (pinfunction "1_1") (pintype "passive"))
    )
    (net (code "70") (name "unconnected-(S6-Pad1)") (class "Default")
      (node (ref "S6") (pin "1") (pinfunction "1_1") (pintype "passive"))
    )
    (net (code "71") (name "unconnected-(S7-Pad1)") (class "Default")
      (node (ref "S7") (pin "1") (pinfunction "1_1") (pintype "passive"))
    )
    (net (code "72") (name "unconnected-(S8-Pad1)") (class "Default")
      (node (ref "S8") (pin "1") (pinfunction "1_1") (pintype "passive"))
    )
    (net (code "73") (name "unconnected-(S9-Pad1)") (class "Default")
      (node (ref "S9") (pin "1") (pinfunction "1_1") (pintype "passive"))
    )
    (net (code "74") (name "unconnected-(S10-Pad1)") (class "Default")
      (node (ref "S10") (pin "1") (pinfunction "1_1") (pintype "passive"))
    )
    (net (code "75") (name "unconnected-(S11-Pad1)") (class "Default")
      (node (ref "S11") (pin "1") (pinfunction "1_1") (pintype "passive"))
    )
    (net (code "76") (name "unconnected-(S12-Pad1)") (class "Default")
      (node (ref "S12") (pin "1") (pinfunction "1_1") (pintype "passive"))
    )
    (net (code "77") (name "unconnected-(U3-PA8{slash}T1C1{slash}MCO-Pad29)") (class "Default")
      (node (ref "U3") (pin "29") (pinfunction "PA8/T1C1/MCO_29") (pintype "passive"))
    )
    (net (code "78") (name "unconnected-(U3-PA15{slash}JTDI{slash}I2S3_WS{slash}JTDI{slash}T2C1ETR{slash}SPI3_NSS-Pad38)") (class "Default")
      (node (ref "U3") (pin "38") (pinfunction "PA15/JTDI/I2S3_WS/JTDI/T2C1ETR/SPI3_NSS_38") (pintype "passive"))
    )
    (net (code "79") (name "unconnected-(U3-PB15{slash}I2S2_SD{slash}T1CH3N{slash}SPI2_MOSI-Pad28)") (class "Default")
      (node (ref "U3") (pin "28") (pinfunction "PB15/I2S2_SD/T1CH3N/SPI2_MOSI_28") (pintype "passive"))
    )
    (net (code "80") (name "unconnected-(U3-VBAT-Pad1)") (class "Default")
      (node (ref "U3") (pin "1") (pinfunction "VBAT_1") (pintype "passive"))
    )
    (net (code "81") (name "unconnected-(U17-RTS-Pad4)") (class "Default")
      (node (ref "U17") (pin "4") (pinfunction "RTS_4") (pintype "passive"))
    )
  )
)
